# xen_teensy_motherboard_8cv8pt_mki.net
KiCad netlist of a schematic drawn in EAGLE
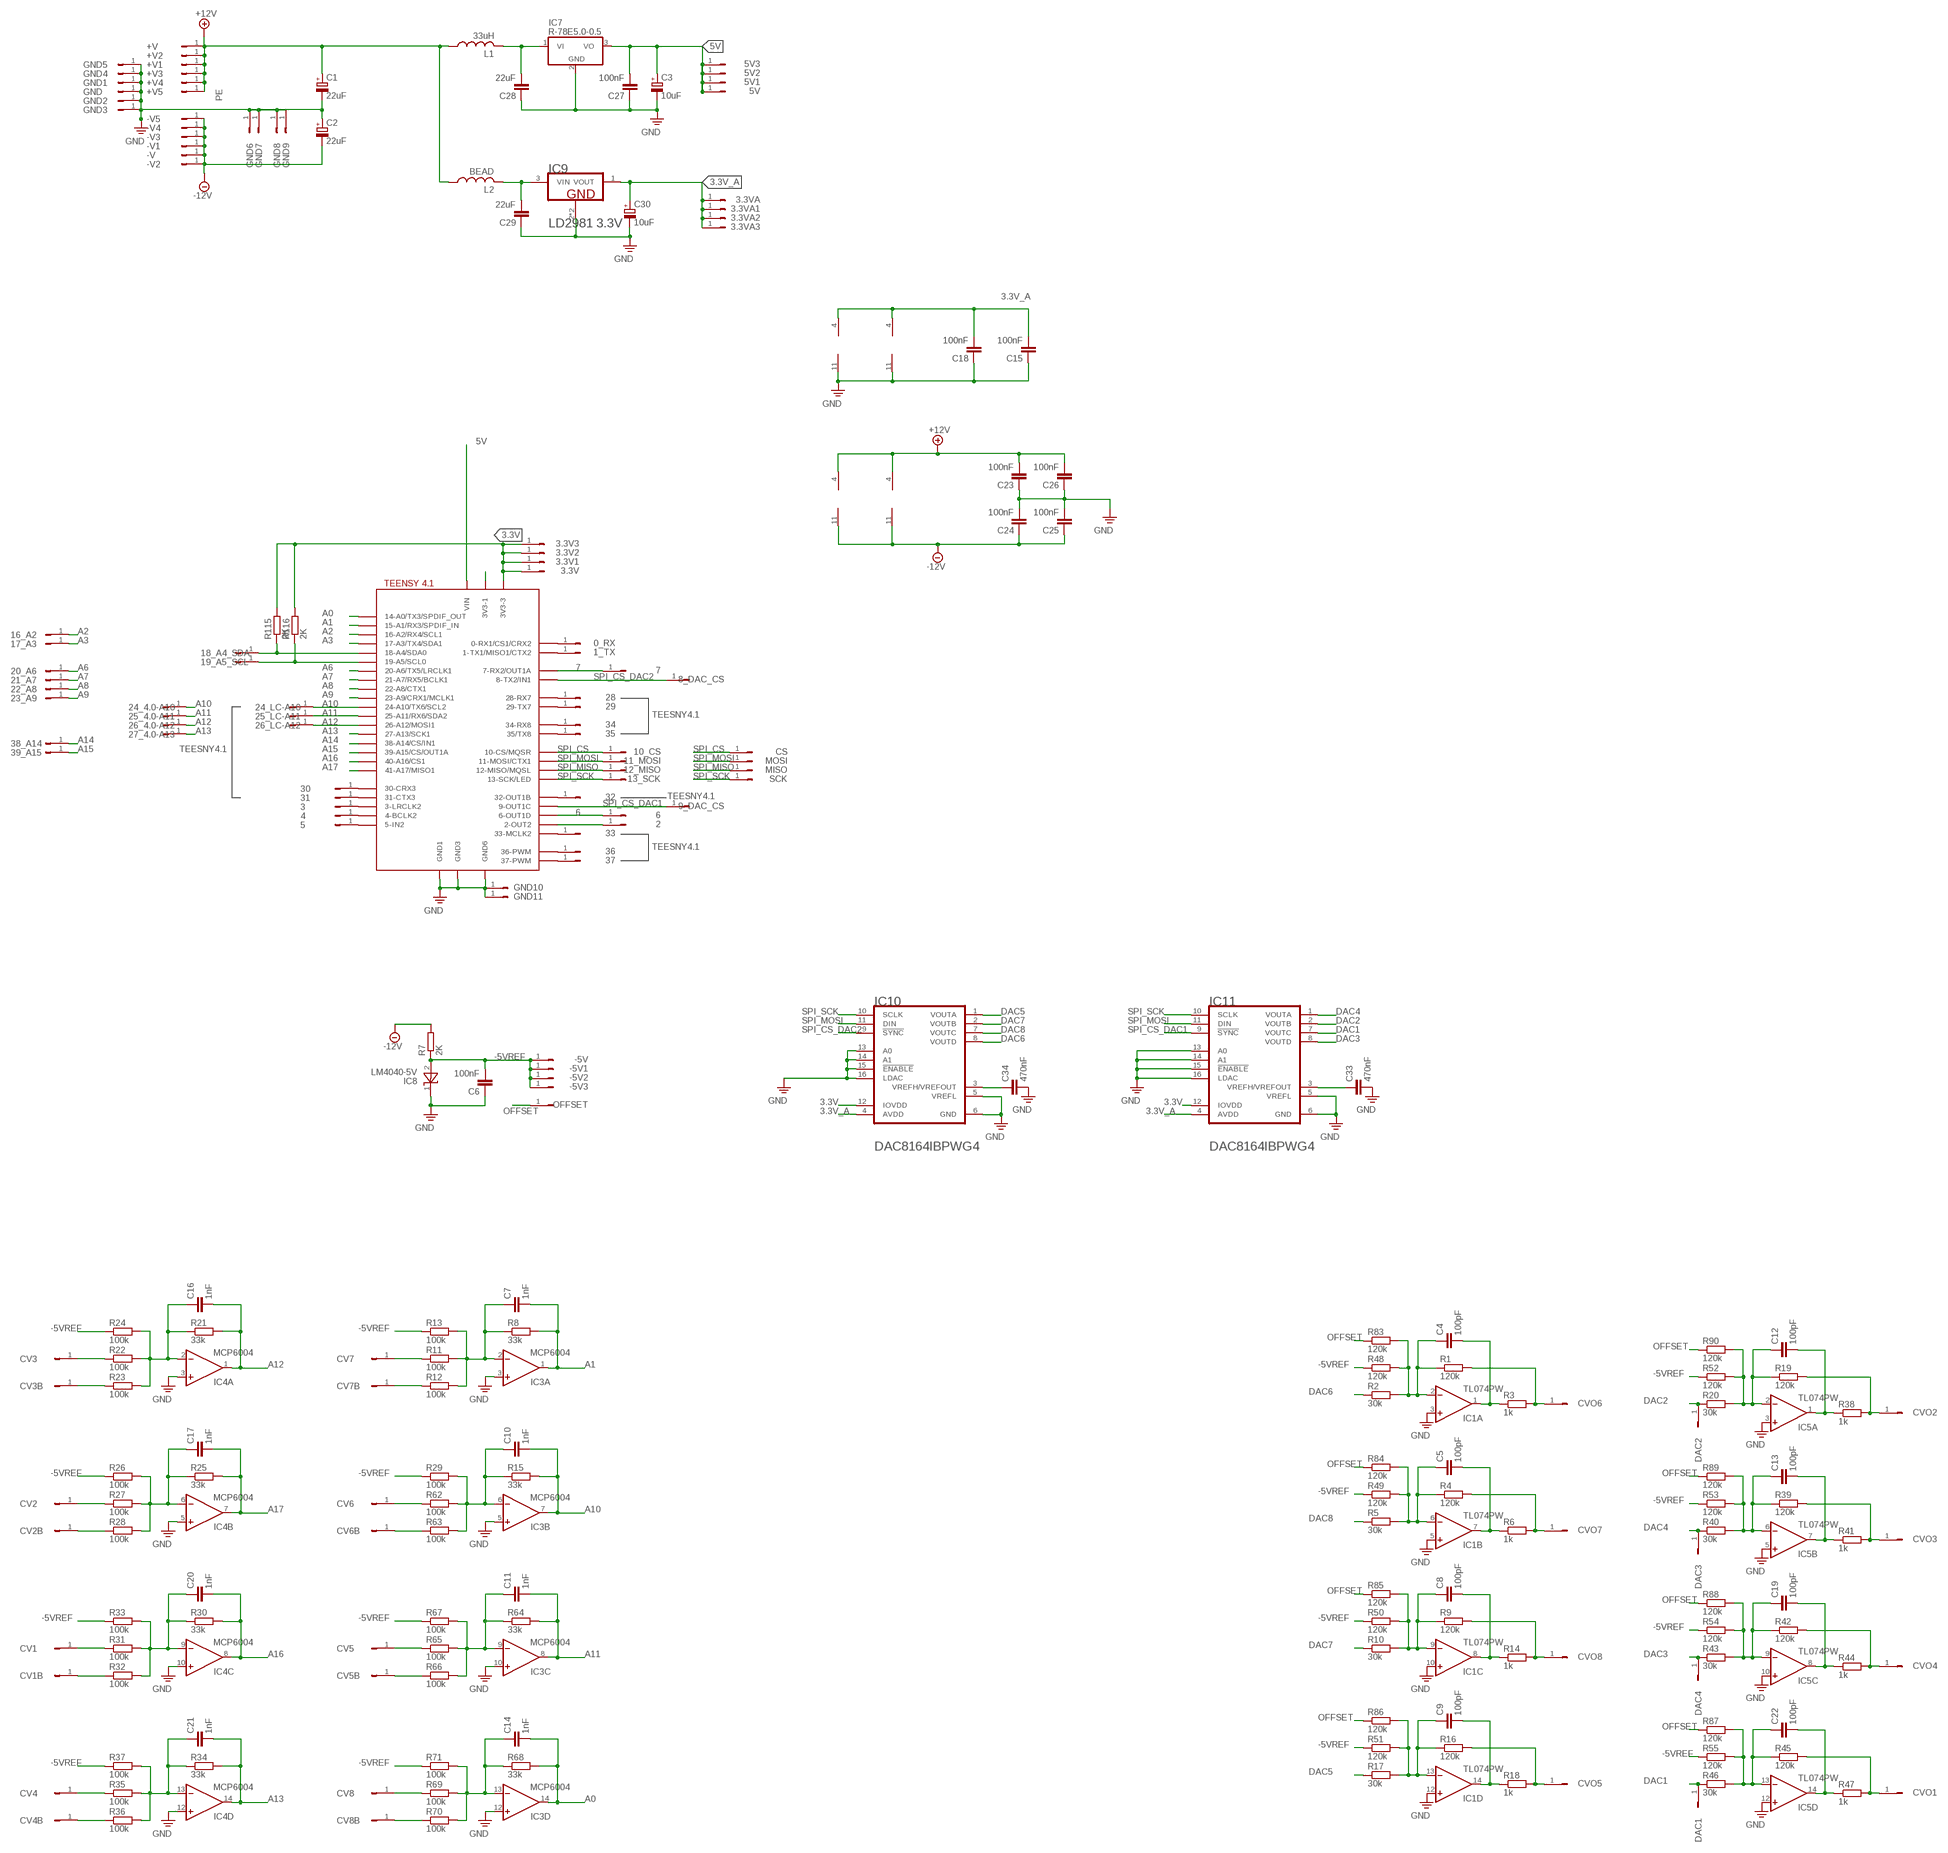
[diagram p0: schematic, sheet 1]

(export (version "E")
  (design (tool "Eeschema 10.0.6"))
  (components
    (comp (ref "+V")
      (value "HEADER/MALE/01")
      (footprint "eagle-import:HEADER_MALE_01")
      (fields (field (name "SPICEPREFIX") "X"))
      (libsource (lib "eagle-import") (part "HEADER/MALE/01"))
    )
    (comp (ref "+V1")
      (value "HEADER/MALE/01")
      (footprint "eagle-import:HEADER_MALE_01")
      (fields (field (name "SPICEPREFIX") "X"))
      (libsource (lib "eagle-import") (part "HEADER/MALE/01"))
    )
    (comp (ref "+V2")
      (value "HEADER/MALE/01")
      (footprint "eagle-import:HEADER_MALE_01")
      (fields (field (name "SPICEPREFIX") "X"))
      (libsource (lib "eagle-import") (part "HEADER/MALE/01"))
    )
    (comp (ref "+V3")
      (value "HEADER/MALE/01")
      (footprint "eagle-import:HEADER_MALE_01")
      (fields (field (name "SPICEPREFIX") "X"))
      (libsource (lib "eagle-import") (part "HEADER/MALE/01"))
    )
    (comp (ref "+V4")
      (value "HEADER/MALE/01")
      (footprint "eagle-import:HEADER_MALE_01")
      (fields (field (name "SPICEPREFIX") "X"))
      (libsource (lib "eagle-import") (part "HEADER/MALE/01"))
    )
    (comp (ref "+V5")
      (value "HEADER/MALE/01")
      (footprint "eagle-import:HEADER_MALE_01")
      (fields (field (name "SPICEPREFIX") "X"))
      (libsource (lib "eagle-import") (part "HEADER/MALE/01"))
    )
    (comp (ref "-5V")
      (value "HEADER/MALE/01")
      (footprint "eagle-import:HEADER_MALE_01")
      (fields (field (name "SPICEPREFIX") "X"))
      (libsource (lib "eagle-import") (part "HEADER/MALE/01"))
    )
    (comp (ref "-5V1")
      (value "HEADER/MALE/01")
      (footprint "eagle-import:HEADER_MALE_01")
      (fields (field (name "SPICEPREFIX") "X"))
      (libsource (lib "eagle-import") (part "HEADER/MALE/01"))
    )
    (comp (ref "-5V2")
      (value "HEADER/MALE/01")
      (footprint "eagle-import:HEADER_MALE_01")
      (fields (field (name "SPICEPREFIX") "X"))
      (libsource (lib "eagle-import") (part "HEADER/MALE/01"))
    )
    (comp (ref "-5V3")
      (value "HEADER/MALE/01")
      (footprint "eagle-import:HEADER_MALE_01")
      (fields (field (name "SPICEPREFIX") "X"))
      (libsource (lib "eagle-import") (part "HEADER/MALE/01"))
    )
    (comp (ref "-V")
      (value "HEADER/MALE/01")
      (footprint "eagle-import:HEADER_MALE_01")
      (fields (field (name "SPICEPREFIX") "X"))
      (libsource (lib "eagle-import") (part "HEADER/MALE/01"))
    )
    (comp (ref "-V1")
      (value "HEADER/MALE/01")
      (footprint "eagle-import:HEADER_MALE_01")
      (fields (field (name "SPICEPREFIX") "X"))
      (libsource (lib "eagle-import") (part "HEADER/MALE/01"))
    )
    (comp (ref "-V2")
      (value "HEADER/MALE/01")
      (footprint "eagle-import:HEADER_MALE_01")
      (fields (field (name "SPICEPREFIX") "X"))
      (libsource (lib "eagle-import") (part "HEADER/MALE/01"))
    )
    (comp (ref "-V3")
      (value "HEADER/MALE/01")
      (footprint "eagle-import:HEADER_MALE_01")
      (fields (field (name "SPICEPREFIX") "X"))
      (libsource (lib "eagle-import") (part "HEADER/MALE/01"))
    )
    (comp (ref "-V4")
      (value "HEADER/MALE/01")
      (footprint "eagle-import:HEADER_MALE_01")
      (fields (field (name "SPICEPREFIX") "X"))
      (libsource (lib "eagle-import") (part "HEADER/MALE/01"))
    )
    (comp (ref "-V5")
      (value "HEADER/MALE/01")
      (footprint "eagle-import:HEADER_MALE_01")
      (fields (field (name "SPICEPREFIX") "X"))
      (libsource (lib "eagle-import") (part "HEADER/MALE/01"))
    )
    (comp (ref "0_RX")
      (value "HEADER/MALE/01")
      (footprint "eagle-import:HEADER_MALE_01")
      (fields (field (name "SPICEPREFIX") "X"))
      (libsource (lib "eagle-import") (part "HEADER/MALE/01"))
    )
    (comp (ref "1_TX")
      (value "HEADER/MALE/01")
      (footprint "eagle-import:HEADER_MALE_01")
      (fields (field (name "SPICEPREFIX") "X"))
      (libsource (lib "eagle-import") (part "HEADER/MALE/01"))
    )
    (comp (ref "2")
      (value "HEADER/MALE/01")
      (footprint "eagle-import:HEADER_MALE_01")
      (fields (field (name "SPICEPREFIX") "X"))
      (libsource (lib "eagle-import") (part "HEADER/MALE/01"))
    )
    (comp (ref "3")
      (value "HEADER/MALE/01")
      (footprint "eagle-import:HEADER_MALE_01")
      (fields (field (name "SPICEPREFIX") "X"))
      (libsource (lib "eagle-import") (part "HEADER/MALE/01"))
    )
    (comp (ref "3.3V")
      (value "HEADER/MALE/01")
      (footprint "eagle-import:HEADER_MALE_01")
      (fields (field (name "SPICEPREFIX") "X"))
      (libsource (lib "eagle-import") (part "HEADER/MALE/01"))
    )
    (comp (ref "3.3V1")
      (value "HEADER/MALE/01")
      (footprint "eagle-import:HEADER_MALE_01")
      (fields (field (name "SPICEPREFIX") "X"))
      (libsource (lib "eagle-import") (part "HEADER/MALE/01"))
    )
    (comp (ref "3.3V2")
      (value "HEADER/MALE/01")
      (footprint "eagle-import:HEADER_MALE_01")
      (fields (field (name "SPICEPREFIX") "X"))
      (libsource (lib "eagle-import") (part "HEADER/MALE/01"))
    )
    (comp (ref "3.3V3")
      (value "HEADER/MALE/01")
      (footprint "eagle-import:HEADER_MALE_01")
      (fields (field (name "SPICEPREFIX") "X"))
      (libsource (lib "eagle-import") (part "HEADER/MALE/01"))
    )
    (comp (ref "3.3VA")
      (value "HEADER/MALE/01")
      (footprint "eagle-import:HEADER_MALE_01")
      (fields (field (name "SPICEPREFIX") "X"))
      (libsource (lib "eagle-import") (part "HEADER/MALE/01"))
    )
    (comp (ref "3.3VA1")
      (value "HEADER/MALE/01")
      (footprint "eagle-import:HEADER_MALE_01")
      (fields (field (name "SPICEPREFIX") "X"))
      (libsource (lib "eagle-import") (part "HEADER/MALE/01"))
    )
    (comp (ref "3.3VA2")
      (value "HEADER/MALE/01")
      (footprint "eagle-import:HEADER_MALE_01")
      (fields (field (name "SPICEPREFIX") "X"))
      (libsource (lib "eagle-import") (part "HEADER/MALE/01"))
    )
    (comp (ref "3.3VA3")
      (value "HEADER/MALE/01")
      (footprint "eagle-import:HEADER_MALE_01")
      (fields (field (name "SPICEPREFIX") "X"))
      (libsource (lib "eagle-import") (part "HEADER/MALE/01"))
    )
    (comp (ref "4")
      (value "HEADER/MALE/01")
      (footprint "eagle-import:HEADER_MALE_01")
      (fields (field (name "SPICEPREFIX") "X"))
      (libsource (lib "eagle-import") (part "HEADER/MALE/01"))
    )
    (comp (ref "5")
      (value "HEADER/MALE/01")
      (footprint "eagle-import:HEADER_MALE_01")
      (fields (field (name "SPICEPREFIX") "X"))
      (libsource (lib "eagle-import") (part "HEADER/MALE/01"))
    )
    (comp (ref "5V")
      (value "HEADER/MALE/01")
      (footprint "eagle-import:HEADER_MALE_01")
      (fields (field (name "SPICEPREFIX") "X"))
      (libsource (lib "eagle-import") (part "HEADER/MALE/01"))
    )
    (comp (ref "5V1")
      (value "HEADER/MALE/01")
      (footprint "eagle-import:HEADER_MALE_01")
      (fields (field (name "SPICEPREFIX") "X"))
      (libsource (lib "eagle-import") (part "HEADER/MALE/01"))
    )
    (comp (ref "5V2")
      (value "HEADER/MALE/01")
      (footprint "eagle-import:HEADER_MALE_01")
      (fields (field (name "SPICEPREFIX") "X"))
      (libsource (lib "eagle-import") (part "HEADER/MALE/01"))
    )
    (comp (ref "5V3")
      (value "HEADER/MALE/01")
      (footprint "eagle-import:HEADER_MALE_01")
      (fields (field (name "SPICEPREFIX") "X"))
      (libsource (lib "eagle-import") (part "HEADER/MALE/01"))
    )
    (comp (ref "6")
      (value "HEADER/MALE/01")
      (footprint "eagle-import:HEADER_MALE_01")
      (fields (field (name "SPICEPREFIX") "X"))
      (libsource (lib "eagle-import") (part "HEADER/MALE/01"))
    )
    (comp (ref "7")
      (value "HEADER/MALE/01")
      (footprint "eagle-import:HEADER_MALE_01")
      (fields (field (name "SPICEPREFIX") "X"))
      (libsource (lib "eagle-import") (part "HEADER/MALE/01"))
    )
    (comp (ref "8_DAC_CS")
      (value "HEADER/MALE/01")
      (footprint "eagle-import:HEADER_MALE_01")
      (fields (field (name "SPICEPREFIX") "X"))
      (libsource (lib "eagle-import") (part "HEADER/MALE/01"))
    )
    (comp (ref "9_DAC_CS")
      (value "HEADER/MALE/01")
      (footprint "eagle-import:HEADER_MALE_01")
      (fields (field (name "SPICEPREFIX") "X"))
      (libsource (lib "eagle-import") (part "HEADER/MALE/01"))
    )
    (comp (ref "10_CS")
      (value "HEADER/MALE/01")
      (footprint "eagle-import:HEADER_MALE_01")
      (fields (field (name "SPICEPREFIX") "X"))
      (libsource (lib "eagle-import") (part "HEADER/MALE/01"))
    )
    (comp (ref "11_MOSI")
      (value "HEADER/MALE/01")
      (footprint "eagle-import:HEADER_MALE_01")
      (fields (field (name "SPICEPREFIX") "X"))
      (libsource (lib "eagle-import") (part "HEADER/MALE/01"))
    )
    (comp (ref "12_MISO")
      (value "HEADER/MALE/01")
      (footprint "eagle-import:HEADER_MALE_01")
      (fields (field (name "SPICEPREFIX") "X"))
      (libsource (lib "eagle-import") (part "HEADER/MALE/01"))
    )
    (comp (ref "13_SCK")
      (value "HEADER/MALE/01")
      (footprint "eagle-import:HEADER_MALE_01")
      (fields (field (name "SPICEPREFIX") "X"))
      (libsource (lib "eagle-import") (part "HEADER/MALE/01"))
    )
    (comp (ref "16_A2")
      (value "HEADER/MALE/01")
      (footprint "eagle-import:HEADER_MALE_01")
      (fields (field (name "SPICEPREFIX") "X"))
      (libsource (lib "eagle-import") (part "HEADER/MALE/01"))
    )
    (comp (ref "17_A3")
      (value "HEADER/MALE/01")
      (footprint "eagle-import:HEADER_MALE_01")
      (fields (field (name "SPICEPREFIX") "X"))
      (libsource (lib "eagle-import") (part "HEADER/MALE/01"))
    )
    (comp (ref "18_A4_SDA")
      (value "HEADER/MALE/01")
      (footprint "eagle-import:HEADER_MALE_01")
      (fields (field (name "SPICEPREFIX") "X"))
      (libsource (lib "eagle-import") (part "HEADER/MALE/01"))
    )
    (comp (ref "19_A5_SCL")
      (value "HEADER/MALE/01")
      (footprint "eagle-import:HEADER_MALE_01")
      (fields (field (name "SPICEPREFIX") "X"))
      (libsource (lib "eagle-import") (part "HEADER/MALE/01"))
    )
    (comp (ref "20_A6")
      (value "HEADER/MALE/01")
      (footprint "eagle-import:HEADER_MALE_01")
      (fields (field (name "SPICEPREFIX") "X"))
      (libsource (lib "eagle-import") (part "HEADER/MALE/01"))
    )
    (comp (ref "21_A7")
      (value "HEADER/MALE/01")
      (footprint "eagle-import:HEADER_MALE_01")
      (fields (field (name "SPICEPREFIX") "X"))
      (libsource (lib "eagle-import") (part "HEADER/MALE/01"))
    )
    (comp (ref "22_A8")
      (value "HEADER/MALE/01")
      (footprint "eagle-import:HEADER_MALE_01")
      (fields (field (name "SPICEPREFIX") "X"))
      (libsource (lib "eagle-import") (part "HEADER/MALE/01"))
    )
    (comp (ref "23_A9")
      (value "HEADER/MALE/01")
      (footprint "eagle-import:HEADER_MALE_01")
      (fields (field (name "SPICEPREFIX") "X"))
      (libsource (lib "eagle-import") (part "HEADER/MALE/01"))
    )
    (comp (ref "24_4.0-A10")
      (value "HEADER/MALE/01")
      (footprint "eagle-import:HEADER_MALE_01")
      (fields (field (name "SPICEPREFIX") "X"))
      (libsource (lib "eagle-import") (part "HEADER/MALE/01"))
    )
    (comp (ref "24_LC-A10")
      (value "HEADER/MALE/01")
      (footprint "eagle-import:HEADER_MALE_01")
      (fields (field (name "SPICEPREFIX") "X"))
      (libsource (lib "eagle-import") (part "HEADER/MALE/01"))
    )
    (comp (ref "25_4.0-A11")
      (value "HEADER/MALE/01")
      (footprint "eagle-import:HEADER_MALE_01")
      (fields (field (name "SPICEPREFIX") "X"))
      (libsource (lib "eagle-import") (part "HEADER/MALE/01"))
    )
    (comp (ref "25_LC-A11")
      (value "HEADER/MALE/01")
      (footprint "eagle-import:HEADER_MALE_01")
      (fields (field (name "SPICEPREFIX") "X"))
      (libsource (lib "eagle-import") (part "HEADER/MALE/01"))
    )
    (comp (ref "26_4.0-A12")
      (value "HEADER/MALE/01")
      (footprint "eagle-import:HEADER_MALE_01")
      (fields (field (name "SPICEPREFIX") "X"))
      (libsource (lib "eagle-import") (part "HEADER/MALE/01"))
    )
    (comp (ref "26_LC-A12")
      (value "HEADER/MALE/01")
      (footprint "eagle-import:HEADER_MALE_01")
      (fields (field (name "SPICEPREFIX") "X"))
      (libsource (lib "eagle-import") (part "HEADER/MALE/01"))
    )
    (comp (ref "27_4.0-A13")
      (value "HEADER/MALE/01")
      (footprint "eagle-import:HEADER_MALE_01")
      (fields (field (name "SPICEPREFIX") "X"))
      (libsource (lib "eagle-import") (part "HEADER/MALE/01"))
    )
    (comp (ref "28")
      (value "HEADER/MALE/01")
      (footprint "eagle-import:HEADER_MALE_01")
      (fields (field (name "SPICEPREFIX") "X"))
      (libsource (lib "eagle-import") (part "HEADER/MALE/01"))
    )
    (comp (ref "29")
      (value "HEADER/MALE/01")
      (footprint "eagle-import:HEADER_MALE_01")
      (fields (field (name "SPICEPREFIX") "X"))
      (libsource (lib "eagle-import") (part "HEADER/MALE/01"))
    )
    (comp (ref "30")
      (value "HEADER/MALE/01")
      (footprint "eagle-import:HEADER_MALE_01")
      (fields (field (name "SPICEPREFIX") "X"))
      (libsource (lib "eagle-import") (part "HEADER/MALE/01"))
    )
    (comp (ref "31")
      (value "HEADER/MALE/01")
      (footprint "eagle-import:HEADER_MALE_01")
      (fields (field (name "SPICEPREFIX") "X"))
      (libsource (lib "eagle-import") (part "HEADER/MALE/01"))
    )
    (comp (ref "32")
      (value "HEADER/MALE/01")
      (footprint "eagle-import:HEADER_MALE_01")
      (fields (field (name "SPICEPREFIX") "X"))
      (libsource (lib "eagle-import") (part "HEADER/MALE/01"))
    )
    (comp (ref "33")
      (value "HEADER/MALE/01")
      (footprint "eagle-import:HEADER_MALE_01")
      (fields (field (name "SPICEPREFIX") "X"))
      (libsource (lib "eagle-import") (part "HEADER/MALE/01"))
    )
    (comp (ref "34")
      (value "HEADER/MALE/01")
      (footprint "eagle-import:HEADER_MALE_01")
      (fields (field (name "SPICEPREFIX") "X"))
      (libsource (lib "eagle-import") (part "HEADER/MALE/01"))
    )
    (comp (ref "35")
      (value "HEADER/MALE/01")
      (footprint "eagle-import:HEADER_MALE_01")
      (fields (field (name "SPICEPREFIX") "X"))
      (libsource (lib "eagle-import") (part "HEADER/MALE/01"))
    )
    (comp (ref "36")
      (value "HEADER/MALE/01")
      (footprint "eagle-import:HEADER_MALE_01")
      (fields (field (name "SPICEPREFIX") "X"))
      (libsource (lib "eagle-import") (part "HEADER/MALE/01"))
    )
    (comp (ref "37")
      (value "HEADER/MALE/01")
      (footprint "eagle-import:HEADER_MALE_01")
      (fields (field (name "SPICEPREFIX") "X"))
      (libsource (lib "eagle-import") (part "HEADER/MALE/01"))
    )
    (comp (ref "38_A14")
      (value "HEADER/MALE/01")
      (footprint "eagle-import:HEADER_MALE_01")
      (fields (field (name "SPICEPREFIX") "X"))
      (libsource (lib "eagle-import") (part "HEADER/MALE/01"))
    )
    (comp (ref "39_A15")
      (value "HEADER/MALE/01")
      (footprint "eagle-import:HEADER_MALE_01")
      (fields (field (name "SPICEPREFIX") "X"))
      (libsource (lib "eagle-import") (part "HEADER/MALE/01"))
    )
    (comp (ref "C1")
      (value "22uF")
      (footprint "eagle-import:SV-C")
      (fields (field (name "SPICEPREFIX") "C"))
      (libsource (lib "eagle-import") (part "CAPACITOR/POLARIZEDSMDC"))
    )
    (comp (ref "C2")
      (value "22uF")
      (footprint "eagle-import:SV-C")
      (fields (field (name "SPICEPREFIX") "C"))
      (libsource (lib "eagle-import") (part "CAPACITOR/POLARIZEDSMDC"))
    )
    (comp (ref "C3")
      (value "10uF")
      (footprint "eagle-import:SV-B")
      (fields (field (name "SPICEPREFIX") "C"))
      (libsource (lib "eagle-import") (part "CAPACITOR/POLARIZEDSMDB"))
    )
    (comp (ref "C4")
      (value "100pF")
      (footprint "eagle-import:C0603")
      (libsource (lib "eagle-import") (part "CAPACITORC0603"))
    )
    (comp (ref "C5")
      (value "100pF")
      (footprint "eagle-import:C0603")
      (libsource (lib "eagle-import") (part "CAPACITORC0603"))
    )
    (comp (ref "C6")
      (value "100nF")
      (footprint "eagle-import:C0603")
      (libsource (lib "eagle-import") (part "CAPACITORC0603"))
    )
    (comp (ref "C7")
      (value "1nF")
      (footprint "eagle-import:C0603")
      (libsource (lib "eagle-import") (part "CAPACITORC0603"))
    )
    (comp (ref "C8")
      (value "100pF")
      (footprint "eagle-import:C0603")
      (libsource (lib "eagle-import") (part "CAPACITORC0603"))
    )
    (comp (ref "C9")
      (value "100pF")
      (footprint "eagle-import:C0603")
      (libsource (lib "eagle-import") (part "CAPACITORC0603"))
    )
    (comp (ref "C10")
      (value "1nF")
      (footprint "eagle-import:C0603")
      (libsource (lib "eagle-import") (part "CAPACITORC0603"))
    )
    (comp (ref "C11")
      (value "1nF")
      (footprint "eagle-import:C0603")
      (libsource (lib "eagle-import") (part "CAPACITORC0603"))
    )
    (comp (ref "C12")
      (value "100pF")
      (footprint "eagle-import:C0603")
      (libsource (lib "eagle-import") (part "CAPACITORC0603"))
    )
    (comp (ref "C13")
      (value "100pF")
      (footprint "eagle-import:C0603")
      (libsource (lib "eagle-import") (part "CAPACITORC0603"))
    )
    (comp (ref "C14")
      (value "1nF")
      (footprint "eagle-import:C0603")
      (libsource (lib "eagle-import") (part "CAPACITORC0603"))
    )
    (comp (ref "C15")
      (value "100nF")
      (footprint "eagle-import:C0603")
      (libsource (lib "eagle-import") (part "CAPACITORC0603"))
    )
    (comp (ref "C16")
      (value "1nF")
      (footprint "eagle-import:C0603")
      (libsource (lib "eagle-import") (part "CAPACITORC0603"))
    )
    (comp (ref "C17")
      (value "1nF")
      (footprint "eagle-import:C0603")
      (libsource (lib "eagle-import") (part "CAPACITORC0603"))
    )
    (comp (ref "C18")
      (value "100nF")
      (footprint "eagle-import:C0603")
      (libsource (lib "eagle-import") (part "CAPACITORC0603"))
    )
    (comp (ref "C19")
      (value "100pF")
      (footprint "eagle-import:C0603")
      (libsource (lib "eagle-import") (part "CAPACITORC0603"))
    )
    (comp (ref "C20")
      (value "1nF")
      (footprint "eagle-import:C0603")
      (libsource (lib "eagle-import") (part "CAPACITORC0603"))
    )
    (comp (ref "C21")
      (value "1nF")
      (footprint "eagle-import:C0603")
      (libsource (lib "eagle-import") (part "CAPACITORC0603"))
    )
    (comp (ref "C22")
      (value "100pF")
      (footprint "eagle-import:C0603")
      (libsource (lib "eagle-import") (part "CAPACITORC0603"))
    )
    (comp (ref "C23")
      (value "100nF")
      (footprint "eagle-import:C0603")
      (libsource (lib "eagle-import") (part "CAPACITORC0603"))
    )
    (comp (ref "C24")
      (value "100nF")
      (footprint "eagle-import:C0603")
      (libsource (lib "eagle-import") (part "CAPACITORC0603"))
    )
    (comp (ref "C25")
      (value "100nF")
      (footprint "eagle-import:C0603")
      (libsource (lib "eagle-import") (part "CAPACITORC0603"))
    )
    (comp (ref "C26")
      (value "100nF")
      (footprint "eagle-import:C0603")
      (libsource (lib "eagle-import") (part "CAPACITORC0603"))
    )
    (comp (ref "C27")
      (value "100nF")
      (footprint "eagle-import:C0603")
      (libsource (lib "eagle-import") (part "CAPACITORC0603"))
    )
    (comp (ref "C28")
      (value "22uF")
      (footprint "eagle-import:C0805")
      (libsource (lib "eagle-import") (part "CAPACITORC0805"))
    )
    (comp (ref "C29")
      (value "22uF")
      (footprint "eagle-import:C0805")
      (libsource (lib "eagle-import") (part "CAPACITORC0805"))
    )
    (comp (ref "C30")
      (value "10uF")
      (footprint "eagle-import:SV-B")
      (fields (field (name "SPICEPREFIX") "C"))
      (libsource (lib "eagle-import") (part "CAPACITOR/POLARIZEDSMDB"))
    )
    (comp (ref "C33")
      (value "470nF")
      (footprint "eagle-import:C0603")
      (libsource (lib "eagle-import") (part "CAPACITORC0603"))
    )
    (comp (ref "C34")
      (value "470nF")
      (footprint "eagle-import:C0603")
      (libsource (lib "eagle-import") (part "CAPACITORC0603"))
    )
    (comp (ref "CS")
      (value "HEADER/MALE/01")
      (footprint "eagle-import:HEADER_MALE_01")
      (fields (field (name "SPICEPREFIX") "X"))
      (libsource (lib "eagle-import") (part "HEADER/MALE/01"))
    )
    (comp (ref "CV1")
      (value "HEADER/MALE/01")
      (footprint "eagle-import:HEADER_MALE_01")
      (fields (field (name "SPICEPREFIX") "X"))
      (libsource (lib "eagle-import") (part "HEADER/MALE/01"))
    )
    (comp (ref "CV1B")
      (value "HEADER/MALE/01")
      (footprint "eagle-import:HEADER_MALE_01")
      (fields (field (name "SPICEPREFIX") "X"))
      (libsource (lib "eagle-import") (part "HEADER/MALE/01"))
    )
    (comp (ref "CV2")
      (value "HEADER/MALE/01")
      (footprint "eagle-import:HEADER_MALE_01")
      (fields (field (name "SPICEPREFIX") "X"))
      (libsource (lib "eagle-import") (part "HEADER/MALE/01"))
    )
    (comp (ref "CV2B")
      (value "HEADER/MALE/01")
      (footprint "eagle-import:HEADER_MALE_01")
      (fields (field (name "SPICEPREFIX") "X"))
      (libsource (lib "eagle-import") (part "HEADER/MALE/01"))
    )
    (comp (ref "CV3")
      (value "HEADER/MALE/01")
      (footprint "eagle-import:HEADER_MALE_01")
      (fields (field (name "SPICEPREFIX") "X"))
      (libsource (lib "eagle-import") (part "HEADER/MALE/01"))
    )
    (comp (ref "CV3B")
      (value "HEADER/MALE/01")
      (footprint "eagle-import:HEADER_MALE_01")
      (fields (field (name "SPICEPREFIX") "X"))
      (libsource (lib "eagle-import") (part "HEADER/MALE/01"))
    )
    (comp (ref "CV4")
      (value "HEADER/MALE/01")
      (footprint "eagle-import:HEADER_MALE_01")
      (fields (field (name "SPICEPREFIX") "X"))
      (libsource (lib "eagle-import") (part "HEADER/MALE/01"))
    )
    (comp (ref "CV4B")
      (value "HEADER/MALE/01")
      (footprint "eagle-import:HEADER_MALE_01")
      (fields (field (name "SPICEPREFIX") "X"))
      (libsource (lib "eagle-import") (part "HEADER/MALE/01"))
    )
    (comp (ref "CV5")
      (value "HEADER/MALE/01")
      (footprint "eagle-import:HEADER_MALE_01")
      (fields (field (name "SPICEPREFIX") "X"))
      (libsource (lib "eagle-import") (part "HEADER/MALE/01"))
    )
    (comp (ref "CV5B")
      (value "HEADER/MALE/01")
      (footprint "eagle-import:HEADER_MALE_01")
      (fields (field (name "SPICEPREFIX") "X"))
      (libsource (lib "eagle-import") (part "HEADER/MALE/01"))
    )
    (comp (ref "CV6")
      (value "HEADER/MALE/01")
      (footprint "eagle-import:HEADER_MALE_01")
      (fields (field (name "SPICEPREFIX") "X"))
      (libsource (lib "eagle-import") (part "HEADER/MALE/01"))
    )
    (comp (ref "CV6B")
      (value "HEADER/MALE/01")
      (footprint "eagle-import:HEADER_MALE_01")
      (fields (field (name "SPICEPREFIX") "X"))
      (libsource (lib "eagle-import") (part "HEADER/MALE/01"))
    )
    (comp (ref "CV7")
      (value "HEADER/MALE/01")
      (footprint "eagle-import:HEADER_MALE_01")
      (fields (field (name "SPICEPREFIX") "X"))
      (libsource (lib "eagle-import") (part "HEADER/MALE/01"))
    )
    (comp (ref "CV7B")
      (value "HEADER/MALE/01")
      (footprint "eagle-import:HEADER_MALE_01")
      (fields (field (name "SPICEPREFIX") "X"))
      (libsource (lib "eagle-import") (part "HEADER/MALE/01"))
    )
    (comp (ref "CV8")
      (value "HEADER/MALE/01")
      (footprint "eagle-import:HEADER_MALE_01")
      (fields (field (name "SPICEPREFIX") "X"))
      (libsource (lib "eagle-import") (part "HEADER/MALE/01"))
    )
    (comp (ref "CV8B")
      (value "HEADER/MALE/01")
      (footprint "eagle-import:HEADER_MALE_01")
      (fields (field (name "SPICEPREFIX") "X"))
      (libsource (lib "eagle-import") (part "HEADER/MALE/01"))
    )
    (comp (ref "CVO1")
      (value "HEADER/MALE/01")
      (footprint "eagle-import:HEADER_MALE_01")
      (fields (field (name "SPICEPREFIX") "X"))
      (libsource (lib "eagle-import") (part "HEADER/MALE/01"))
    )
    (comp (ref "CVO2")
      (value "HEADER/MALE/01")
      (footprint "eagle-import:HEADER_MALE_01")
      (fields (field (name "SPICEPREFIX") "X"))
      (libsource (lib "eagle-import") (part "HEADER/MALE/01"))
    )
    (comp (ref "CVO3")
      (value "HEADER/MALE/01")
      (footprint "eagle-import:HEADER_MALE_01")
      (fields (field (name "SPICEPREFIX") "X"))
      (libsource (lib "eagle-import") (part "HEADER/MALE/01"))
    )
    (comp (ref "CVO4")
      (value "HEADER/MALE/01")
      (footprint "eagle-import:HEADER_MALE_01")
      (fields (field (name "SPICEPREFIX") "X"))
      (libsource (lib "eagle-import") (part "HEADER/MALE/01"))
    )
    (comp (ref "CVO5")
      (value "HEADER/MALE/01")
      (footprint "eagle-import:HEADER_MALE_01")
      (fields (field (name "SPICEPREFIX") "X"))
      (libsource (lib "eagle-import") (part "HEADER/MALE/01"))
    )
    (comp (ref "CVO6")
      (value "HEADER/MALE/01")
      (footprint "eagle-import:HEADER_MALE_01")
      (fields (field (name "SPICEPREFIX") "X"))
      (libsource (lib "eagle-import") (part "HEADER/MALE/01"))
    )
    (comp (ref "CVO7")
      (value "HEADER/MALE/01")
      (footprint "eagle-import:HEADER_MALE_01")
      (fields (field (name "SPICEPREFIX") "X"))
      (libsource (lib "eagle-import") (part "HEADER/MALE/01"))
    )
    (comp (ref "CVO8")
      (value "HEADER/MALE/01")
      (footprint "eagle-import:HEADER_MALE_01")
      (fields (field (name "SPICEPREFIX") "X"))
      (libsource (lib "eagle-import") (part "HEADER/MALE/01"))
    )
    (comp (ref "DAC1")
      (value "HEADER/MALE/01")
      (footprint "eagle-import:HEADER_MALE_01")
      (fields (field (name "SPICEPREFIX") "X"))
      (libsource (lib "eagle-import") (part "HEADER/MALE/01"))
    )
    (comp (ref "DAC2")
      (value "HEADER/MALE/01")
      (footprint "eagle-import:HEADER_MALE_01")
      (fields (field (name "SPICEPREFIX") "X"))
      (libsource (lib "eagle-import") (part "HEADER/MALE/01"))
    )
    (comp (ref "DAC3")
      (value "HEADER/MALE/01")
      (footprint "eagle-import:HEADER_MALE_01")
      (fields (field (name "SPICEPREFIX") "X"))
      (libsource (lib "eagle-import") (part "HEADER/MALE/01"))
    )
    (comp (ref "DAC4")
      (value "HEADER/MALE/01")
      (footprint "eagle-import:HEADER_MALE_01")
      (fields (field (name "SPICEPREFIX") "X"))
      (libsource (lib "eagle-import") (part "HEADER/MALE/01"))
    )
    (comp (ref "GND")
      (value "HEADER/MALE/01")
      (footprint "eagle-import:HEADER_MALE_01")
      (fields (field (name "SPICEPREFIX") "X"))
      (libsource (lib "eagle-import") (part "HEADER/MALE/01"))
    )
    (comp (ref "GND1")
      (value "HEADER/MALE/01")
      (footprint "eagle-import:HEADER_MALE_01")
      (fields (field (name "SPICEPREFIX") "X"))
      (libsource (lib "eagle-import") (part "HEADER/MALE/01"))
    )
    (comp (ref "GND2")
      (value "HEADER/MALE/01")
      (footprint "eagle-import:HEADER_MALE_01")
      (fields (field (name "SPICEPREFIX") "X"))
      (libsource (lib "eagle-import") (part "HEADER/MALE/01"))
    )
    (comp (ref "GND3")
      (value "HEADER/MALE/01")
      (footprint "eagle-import:HEADER_MALE_01")
      (fields (field (name "SPICEPREFIX") "X"))
      (libsource (lib "eagle-import") (part "HEADER/MALE/01"))
    )
    (comp (ref "GND4")
      (value "HEADER/MALE/01")
      (footprint "eagle-import:HEADER_MALE_01")
      (fields (field (name "SPICEPREFIX") "X"))
      (libsource (lib "eagle-import") (part "HEADER/MALE/01"))
    )
    (comp (ref "GND5")
      (value "HEADER/MALE/01")
      (footprint "eagle-import:HEADER_MALE_01")
      (fields (field (name "SPICEPREFIX") "X"))
      (libsource (lib "eagle-import") (part "HEADER/MALE/01"))
    )
    (comp (ref "GND6")
      (value "HEADER/MALE/01")
      (footprint "eagle-import:HEADER_MALE_01")
      (fields (field (name "SPICEPREFIX") "X"))
      (libsource (lib "eagle-import") (part "HEADER/MALE/01"))
    )
    (comp (ref "GND7")
      (value "HEADER/MALE/01")
      (footprint "eagle-import:HEADER_MALE_01")
      (fields (field (name "SPICEPREFIX") "X"))
      (libsource (lib "eagle-import") (part "HEADER/MALE/01"))
    )
    (comp (ref "GND8")
      (value "HEADER/MALE/01")
      (footprint "eagle-import:HEADER_MALE_01")
      (fields (field (name "SPICEPREFIX") "X"))
      (libsource (lib "eagle-import") (part "HEADER/MALE/01"))
    )
    (comp (ref "GND9")
      (value "HEADER/MALE/01")
      (footprint "eagle-import:HEADER_MALE_01")
      (fields (field (name "SPICEPREFIX") "X"))
      (libsource (lib "eagle-import") (part "HEADER/MALE/01"))
    )
    (comp (ref "GND10")
      (value "HEADER/MALE/01")
      (footprint "eagle-import:HEADER_MALE_01")
      (fields (field (name "SPICEPREFIX") "X"))
      (libsource (lib "eagle-import") (part "HEADER/MALE/01"))
    )
    (comp (ref "GND11")
      (value "HEADER/MALE/01")
      (footprint "eagle-import:HEADER_MALE_01")
      (fields (field (name "SPICEPREFIX") "X"))
      (libsource (lib "eagle-import") (part "HEADER/MALE/01"))
    )
    (comp (ref "IC1")
      (value "TL074PW")
      (footprint "eagle-import:TSSOP14")
      (libsource (lib "eagle-import") (part "TL074PW"))
    )
    (comp (ref "IC3")
      (value "MCP6004")
      (footprint "eagle-import:TSSOP14")
      (libsource (lib "eagle-import") (part "TL074PW"))
    )
    (comp (ref "IC4")
      (value "MCP6004")
      (footprint "eagle-import:TSSOP14")
      (libsource (lib "eagle-import") (part "TL074PW"))
    )
    (comp (ref "IC5")
      (value "TL074PW")
      (footprint "eagle-import:TSSOP14")
      (libsource (lib "eagle-import") (part "TL074PW"))
    )
    (comp (ref "IC6")
      (value "TEENSY41-OUTER")
      (footprint "eagle-import:TENNSY41-OUTER")
      (libsource (lib "eagle-import") (part "TEENSY41-OUTER"))
    )
    (comp (ref "IC7")
      (value "R-78E5.0-0.5")
      (footprint "eagle-import:WE78")
      (libsource (lib "eagle-import") (part "WE173950378"))
    )
    (comp (ref "IC8")
      (value "LM4040-5V")
      (footprint "eagle-import:SOT-23")
      (libsource (lib "eagle-import") (part "LM4040CYM3-2.5"))
    )
    (comp (ref "IC9")
      (value "LD2981 3.3V")
      (footprint "eagle-import:LD2981-SOT89")
      (fields (field (name "MF") "STMicroelectronics") (field (name "MPN") "LD2981CU33TR"))
      (libsource (lib "eagle-import") (part "LD2981LD2981-SOT89"))
    )
    (comp (ref "IC10")
      (value "DAC8164")
      (footprint "eagle-import:TEXAS_INSTRUMENTS_DAC8164IBPWG4_1")
      (fields (field (name "MF") "Texas Instruments") (field (name "MPN") "DAC8164IBPWG4"))
      (libsource (lib "eagle-import") (part "TEXAS_INSTRUMENTS_DAC8164IBPWG4TEXAS_INSTRUMENTS_DAC8164IBPWG4_0_1"))
    )
    (comp (ref "IC11")
      (value "DAC8164")
      (footprint "eagle-import:TEXAS_INSTRUMENTS_DAC8164IBPWG4_1")
      (fields (field (name "MF") "Texas Instruments") (field (name "MPN") "DAC8164IBPWG4"))
      (libsource (lib "eagle-import") (part "TEXAS_INSTRUMENTS_DAC8164IBPWG4TEXAS_INSTRUMENTS_DAC8164IBPWG4_0_1"))
    )
    (comp (ref "L1")
      (value "33uH")
      (footprint "eagle-import:L2012C")
      (libsource (lib "eagle-import") (part "INDUCTORL2012C"))
    )
    (comp (ref "L2")
      (value "BEAD")
      (footprint "eagle-import:R0603")
      (libsource (lib "eagle-import") (part "INDUCTORL0603"))
    )
    (comp (ref "MISO")
      (value "HEADER/MALE/01")
      (footprint "eagle-import:HEADER_MALE_01")
      (fields (field (name "SPICEPREFIX") "X"))
      (libsource (lib "eagle-import") (part "HEADER/MALE/01"))
    )
    (comp (ref "MOSI")
      (value "HEADER/MALE/01")
      (footprint "eagle-import:HEADER_MALE_01")
      (fields (field (name "SPICEPREFIX") "X"))
      (libsource (lib "eagle-import") (part "HEADER/MALE/01"))
    )
    (comp (ref "OFFSET")
      (value "HEADER/MALE/01")
      (footprint "eagle-import:HEADER_MALE_01")
      (fields (field (name "SPICEPREFIX") "X"))
      (libsource (lib "eagle-import") (part "HEADER/MALE/01"))
    )
    (comp (ref "R1")
      (value "120k")
      (footprint "eagle-import:R0603")
      (libsource (lib "eagle-import") (part "RESISTOR"))
    )
    (comp (ref "R2")
      (value "30k")
      (footprint "eagle-import:R0603")
      (libsource (lib "eagle-import") (part "RESISTOR"))
    )
    (comp (ref "R3")
      (value "1k")
      (footprint "eagle-import:R0603")
      (libsource (lib "eagle-import") (part "RESISTOR"))
    )
    (comp (ref "R4")
      (value "120k")
      (footprint "eagle-import:R0603")
      (libsource (lib "eagle-import") (part "RESISTOR"))
    )
    (comp (ref "R5")
      (value "30k")
      (footprint "eagle-import:R0603")
      (libsource (lib "eagle-import") (part "RESISTOR"))
    )
    (comp (ref "R6")
      (value "1k")
      (footprint "eagle-import:R0603")
      (libsource (lib "eagle-import") (part "RESISTOR"))
    )
    (comp (ref "R7")
      (value "2K")
      (footprint "eagle-import:R0603")
      (libsource (lib "eagle-import") (part "RESISTOR"))
    )
    (comp (ref "R8")
      (value "33k")
      (footprint "eagle-import:R0603")
      (libsource (lib "eagle-import") (part "RESISTOR"))
    )
    (comp (ref "R9")
      (value "120k")
      (footprint "eagle-import:R0603")
      (libsource (lib "eagle-import") (part "RESISTOR"))
    )
    (comp (ref "R10")
      (value "30k")
      (footprint "eagle-import:R0603")
      (libsource (lib "eagle-import") (part "RESISTOR"))
    )
    (comp (ref "R11")
      (value "100k")
      (footprint "eagle-import:R0603")
      (libsource (lib "eagle-import") (part "RESISTOR"))
    )
    (comp (ref "R12")
      (value "100k")
      (footprint "eagle-import:R0603")
      (libsource (lib "eagle-import") (part "RESISTOR"))
    )
    (comp (ref "R13")
      (value "100k")
      (footprint "eagle-import:R0603")
      (libsource (lib "eagle-import") (part "RESISTOR"))
    )
    (comp (ref "R14")
      (value "1k")
      (footprint "eagle-import:R0603")
      (libsource (lib "eagle-import") (part "RESISTOR"))
    )
    (comp (ref "R15")
      (value "33k")
      (footprint "eagle-import:R0603")
      (libsource (lib "eagle-import") (part "RESISTOR"))
    )
    (comp (ref "R16")
      (value "120k")
      (footprint "eagle-import:R0603")
      (libsource (lib "eagle-import") (part "RESISTOR"))
    )
    (comp (ref "R17")
      (value "30k")
      (footprint "eagle-import:R0603")
      (libsource (lib "eagle-import") (part "RESISTOR"))
    )
    (comp (ref "R18")
      (value "1k")
      (footprint "eagle-import:R0603")
      (libsource (lib "eagle-import") (part "RESISTOR"))
    )
    (comp (ref "R19")
      (value "120k")
      (footprint "eagle-import:R0603")
      (libsource (lib "eagle-import") (part "RESISTOR"))
    )
    (comp (ref "R20")
      (value "30k")
      (footprint "eagle-import:R0603")
      (libsource (lib "eagle-import") (part "RESISTOR"))
    )
    (comp (ref "R21")
      (value "33k")
      (footprint "eagle-import:R0603")
      (libsource (lib "eagle-import") (part "RESISTOR"))
    )
    (comp (ref "R22")
      (value "100k")
      (footprint "eagle-import:R0603")
      (libsource (lib "eagle-import") (part "RESISTOR"))
    )
    (comp (ref "R23")
      (value "100k")
      (footprint "eagle-import:R0603")
      (libsource (lib "eagle-import") (part "RESISTOR"))
    )
    (comp (ref "R24")
      (value "100k")
      (footprint "eagle-import:R0603")
      (libsource (lib "eagle-import") (part "RESISTOR"))
    )
    (comp (ref "R25")
      (value "33k")
      (footprint "eagle-import:R0603")
      (libsource (lib "eagle-import") (part "RESISTOR"))
    )
    (comp (ref "R26")
      (value "100k")
      (footprint "eagle-import:R0603")
      (libsource (lib "eagle-import") (part "RESISTOR"))
    )
    (comp (ref "R27")
      (value "100k")
      (footprint "eagle-import:R0603")
      (libsource (lib "eagle-import") (part "RESISTOR"))
    )
    (comp (ref "R28")
      (value "100k")
      (footprint "eagle-import:R0603")
      (libsource (lib "eagle-import") (part "RESISTOR"))
    )
    (comp (ref "R29")
      (value "100k")
      (footprint "eagle-import:R0603")
      (libsource (lib "eagle-import") (part "RESISTOR"))
    )
    (comp (ref "R30")
      (value "33k")
      (footprint "eagle-import:R0603")
      (libsource (lib "eagle-import") (part "RESISTOR"))
    )
    (comp (ref "R31")
      (value "100k")
      (footprint "eagle-import:R0603")
      (libsource (lib "eagle-import") (part "RESISTOR"))
    )
    (comp (ref "R32")
      (value "100k")
      (footprint "eagle-import:R0603")
      (libsource (lib "eagle-import") (part "RESISTOR"))
    )
    (comp (ref "R33")
      (value "100k")
      (footprint "eagle-import:R0603")
      (libsource (lib "eagle-import") (part "RESISTOR"))
    )
    (comp (ref "R34")
      (value "33k")
      (footprint "eagle-import:R0603")
      (libsource (lib "eagle-import") (part "RESISTOR"))
    )
    (comp (ref "R35")
      (value "100k")
      (footprint "eagle-import:R0603")
      (libsource (lib "eagle-import") (part "RESISTOR"))
    )
    (comp (ref "R36")
      (value "100k")
      (footprint "eagle-import:R0603")
      (libsource (lib "eagle-import") (part "RESISTOR"))
    )
    (comp (ref "R37")
      (value "100k")
      (footprint "eagle-import:R0603")
      (libsource (lib "eagle-import") (part "RESISTOR"))
    )
    (comp (ref "R38")
      (value "1k")
      (footprint "eagle-import:R0603")
      (libsource (lib "eagle-import") (part "RESISTOR"))
    )
    (comp (ref "R39")
      (value "120k")
      (footprint "eagle-import:R0603")
      (libsource (lib "eagle-import") (part "RESISTOR"))
    )
    (comp (ref "R40")
      (value "30k")
      (footprint "eagle-import:R0603")
      (libsource (lib "eagle-import") (part "RESISTOR"))
    )
    (comp (ref "R41")
      (value "1k")
      (footprint "eagle-import:R0603")
      (libsource (lib "eagle-import") (part "RESISTOR"))
    )
    (comp (ref "R42")
      (value "120k")
      (footprint "eagle-import:R0603")
      (libsource (lib "eagle-import") (part "RESISTOR"))
    )
    (comp (ref "R43")
      (value "30k")
      (footprint "eagle-import:R0603")
      (libsource (lib "eagle-import") (part "RESISTOR"))
    )
    (comp (ref "R44")
      (value "1k")
      (footprint "eagle-import:R0603")
      (libsource (lib "eagle-import") (part "RESISTOR"))
    )
    (comp (ref "R45")
      (value "120k")
      (footprint "eagle-import:R0603")
      (libsource (lib "eagle-import") (part "RESISTOR"))
    )
    (comp (ref "R46")
      (value "30k")
      (footprint "eagle-import:R0603")
      (libsource (lib "eagle-import") (part "RESISTOR"))
    )
    (comp (ref "R47")
      (value "1k")
      (footprint "eagle-import:R0603")
      (libsource (lib "eagle-import") (part "RESISTOR"))
    )
    (comp (ref "R48")
      (value "120k")
      (footprint "eagle-import:R0603")
      (libsource (lib "eagle-import") (part "RESISTOR"))
    )
    (comp (ref "R49")
      (value "120k")
      (footprint "eagle-import:R0603")
      (libsource (lib "eagle-import") (part "RESISTOR"))
    )
    (comp (ref "R50")
      (value "120k")
      (footprint "eagle-import:R0603")
      (libsource (lib "eagle-import") (part "RESISTOR"))
    )
    (comp (ref "R51")
      (value "120k")
      (footprint "eagle-import:R0603")
      (libsource (lib "eagle-import") (part "RESISTOR"))
    )
    (comp (ref "R52")
      (value "120k")
      (footprint "eagle-import:R0603")
      (libsource (lib "eagle-import") (part "RESISTOR"))
    )
    (comp (ref "R53")
      (value "120k")
      (footprint "eagle-import:R0603")
      (libsource (lib "eagle-import") (part "RESISTOR"))
    )
    (comp (ref "R54")
      (value "120k")
      (footprint "eagle-import:R0603")
      (libsource (lib "eagle-import") (part "RESISTOR"))
    )
    (comp (ref "R55")
      (value "120k")
      (footprint "eagle-import:R0603")
      (libsource (lib "eagle-import") (part "RESISTOR"))
    )
    (comp (ref "R62")
      (value "100k")
      (footprint "eagle-import:R0603")
      (libsource (lib "eagle-import") (part "RESISTOR"))
    )
    (comp (ref "R63")
      (value "100k")
      (footprint "eagle-import:R0603")
      (libsource (lib "eagle-import") (part "RESISTOR"))
    )
    (comp (ref "R64")
      (value "33k")
      (footprint "eagle-import:R0603")
      (libsource (lib "eagle-import") (part "RESISTOR"))
    )
    (comp (ref "R65")
      (value "100k")
      (footprint "eagle-import:R0603")
      (libsource (lib "eagle-import") (part "RESISTOR"))
    )
    (comp (ref "R66")
      (value "100k")
      (footprint "eagle-import:R0603")
      (libsource (lib "eagle-import") (part "RESISTOR"))
    )
    (comp (ref "R67")
      (value "100k")
      (footprint "eagle-import:R0603")
      (libsource (lib "eagle-import") (part "RESISTOR"))
    )
    (comp (ref "R68")
      (value "33k")
      (footprint "eagle-import:R0603")
      (libsource (lib "eagle-import") (part "RESISTOR"))
    )
    (comp (ref "R69")
      (value "100k")
      (footprint "eagle-import:R0603")
      (libsource (lib "eagle-import") (part "RESISTOR"))
    )
    (comp (ref "R70")
      (value "100k")
      (footprint "eagle-import:R0603")
      (libsource (lib "eagle-import") (part "RESISTOR"))
    )
    (comp (ref "R71")
      (value "100k")
      (footprint "eagle-import:R0603")
      (libsource (lib "eagle-import") (part "RESISTOR"))
    )
    (comp (ref "R83")
      (value "120k")
      (footprint "eagle-import:R0603")
      (libsource (lib "eagle-import") (part "RESISTOR"))
    )
    (comp (ref "R84")
      (value "120k")
      (footprint "eagle-import:R0603")
      (libsource (lib "eagle-import") (part "RESISTOR"))
    )
    (comp (ref "R85")
      (value "120k")
      (footprint "eagle-import:R0603")
      (libsource (lib "eagle-import") (part "RESISTOR"))
    )
    (comp (ref "R86")
      (value "120k")
      (footprint "eagle-import:R0603")
      (libsource (lib "eagle-import") (part "RESISTOR"))
    )
    (comp (ref "R87")
      (value "120k")
      (footprint "eagle-import:R0603")
      (libsource (lib "eagle-import") (part "RESISTOR"))
    )
    (comp (ref "R88")
      (value "120k")
      (footprint "eagle-import:R0603")
      (libsource (lib "eagle-import") (part "RESISTOR"))
    )
    (comp (ref "R89")
      (value "120k")
      (footprint "eagle-import:R0603")
      (libsource (lib "eagle-import") (part "RESISTOR"))
    )
    (comp (ref "R90")
      (value "120k")
      (footprint "eagle-import:R0603")
      (libsource (lib "eagle-import") (part "RESISTOR"))
    )
    (comp (ref "R115")
      (value "2K")
      (footprint "eagle-import:R0603")
      (libsource (lib "eagle-import") (part "RESISTOR"))
    )
    (comp (ref "R116")
      (value "2K")
      (footprint "eagle-import:R0603")
      (libsource (lib "eagle-import") (part "RESISTOR"))
    )
    (comp (ref "SCK")
      (value "HEADER/MALE/01")
      (footprint "eagle-import:HEADER_MALE_01")
      (fields (field (name "SPICEPREFIX") "X"))
      (libsource (lib "eagle-import") (part "HEADER/MALE/01"))
    )
  )
  (nets
    (net (code "1") (name "+12V") (class "Default")
      (node (ref "+V") (pin "1") (pinfunction "3_1") (pintype "passive"))
      (node (ref "+V1") (pin "1") (pinfunction "3_1") (pintype "passive"))
      (node (ref "+V2") (pin "1") (pinfunction "3_1") (pintype "passive"))
      (node (ref "+V3") (pin "1") (pinfunction "3_1") (pintype "passive"))
      (node (ref "+V4") (pin "1") (pinfunction "3_1") (pintype "passive"))
      (node (ref "+V5") (pin "1") (pinfunction "3_1") (pintype "passive"))
      (node (ref "C1") (pin "+") (pinfunction "+_+") (pintype "passive"))
      (node (ref "C23") (pin "2") (pinfunction "2_2") (pintype "passive"))
      (node (ref "C26") (pin "2") (pinfunction "2_2") (pintype "passive"))
      (node (ref "IC1") (pin "4") (pinfunction "V+_4") (pintype "power_in"))
      (node (ref "IC5") (pin "4") (pinfunction "V+_4") (pintype "power_in"))
      (node (ref "L1") (pin "1") (pinfunction "1_1") (pintype "passive"))
      (node (ref "L2") (pin "1") (pinfunction "1_1") (pintype "passive"))
    )
    (net (code "2") (name "-12V") (class "Default")
      (node (ref "-V") (pin "1") (pinfunction "3_1") (pintype "passive"))
      (node (ref "-V1") (pin "1") (pinfunction "3_1") (pintype "passive"))
      (node (ref "-V2") (pin "1") (pinfunction "3_1") (pintype "passive"))
      (node (ref "-V3") (pin "1") (pinfunction "3_1") (pintype "passive"))
      (node (ref "-V4") (pin "1") (pinfunction "3_1") (pintype "passive"))
      (node (ref "-V5") (pin "1") (pinfunction "3_1") (pintype "passive"))
      (node (ref "C2") (pin "-") (pinfunction "-_-") (pintype "passive"))
      (node (ref "C24") (pin "1") (pinfunction "1_1") (pintype "passive"))
      (node (ref "C25") (pin "1") (pinfunction "1_1") (pintype "passive"))
      (node (ref "IC1") (pin "11") (pinfunction "V-_11") (pintype "power_in"))
      (node (ref "IC5") (pin "11") (pinfunction "V-_11") (pintype "power_in"))
      (node (ref "R7") (pin "2") (pinfunction "2_2") (pintype "passive"))
    )
    (net (code "3") (name "/-5VREF") (class "Default")
      (node (ref "-5V") (pin "1") (pinfunction "3_1") (pintype "passive"))
      (node (ref "-5V1") (pin "1") (pinfunction "3_1") (pintype "passive"))
      (node (ref "-5V2") (pin "1") (pinfunction "3_1") (pintype "passive"))
      (node (ref "-5V3") (pin "1") (pinfunction "3_1") (pintype "passive"))
      (node (ref "C6") (pin "2") (pinfunction "2_2") (pintype "passive"))
      (node (ref "IC8") (pin "2") (pinfunction "A_2") (pintype "output"))
      (node (ref "R13") (pin "1") (pinfunction "1_1") (pintype "passive"))
      (node (ref "R24") (pin "1") (pinfunction "1_1") (pintype "passive"))
      (node (ref "R26") (pin "1") (pinfunction "1_1") (pintype "passive"))
      (node (ref "R29") (pin "1") (pinfunction "1_1") (pintype "passive"))
      (node (ref "R33") (pin "1") (pinfunction "1_1") (pintype "passive"))
      (node (ref "R37") (pin "1") (pinfunction "1_1") (pintype "passive"))
      (node (ref "R48") (pin "1") (pinfunction "1_1") (pintype "passive"))
      (node (ref "R49") (pin "1") (pinfunction "1_1") (pintype "passive"))
      (node (ref "R50") (pin "1") (pinfunction "1_1") (pintype "passive"))
      (node (ref "R51") (pin "1") (pinfunction "1_1") (pintype "passive"))
      (node (ref "R52") (pin "1") (pinfunction "1_1") (pintype "passive"))
      (node (ref "R53") (pin "1") (pinfunction "1_1") (pintype "passive"))
      (node (ref "R54") (pin "1") (pinfunction "1_1") (pintype "passive"))
      (node (ref "R55") (pin "1") (pinfunction "1_1") (pintype "passive"))
      (node (ref "R67") (pin "1") (pinfunction "1_1") (pintype "passive"))
      (node (ref "R7") (pin "1") (pinfunction "1_1") (pintype "passive"))
      (node (ref "R71") (pin "1") (pinfunction "1_1") (pintype "passive"))
    )
    (net (code "4") (name "/6") (class "Default")
      (node (ref "6") (pin "1") (pinfunction "3_1") (pintype "passive"))
      (node (ref "IC6") (pin "6-OUT1D") (pinfunction "6-OUT1D_6-OUT1D") (pintype "bidirectional"))
    )
    (net (code "5") (name "/7") (class "Default")
      (node (ref "7") (pin "1") (pinfunction "3_1") (pintype "passive"))
      (node (ref "IC6") (pin "7-RX2/OUT1A") (pinfunction "7-RX2/OUT1A_7-RX2/OUT1A") (pintype "bidirectional"))
    )
    (net (code "6") (name "/A0") (class "Default")
      (node (ref "C14") (pin "2") (pinfunction "2_2") (pintype "passive"))
      (node (ref "IC3") (pin "14") (pinfunction "OUT_14") (pintype "output"))
      (node (ref "IC6") (pin "14-A0/TX3/SPDIF_OUT") (pinfunction "14-A0/TX3/SPDIF_OUT_14-A0/TX3/SPDIF_OUT") (pintype "bidirectional"))
      (node (ref "R68") (pin "2") (pinfunction "2_2") (pintype "passive"))
    )
    (net (code "7") (name "/A1") (class "Default")
      (node (ref "C7") (pin "2") (pinfunction "2_2") (pintype "passive"))
      (node (ref "IC3") (pin "1") (pinfunction "OUT_1") (pintype "output"))
      (node (ref "IC6") (pin "15-A1/RX3/SPDIF_IN") (pinfunction "15-A1/RX3/SPDIF_IN_15-A1/RX3/SPDIF_IN") (pintype "bidirectional"))
      (node (ref "R8") (pin "2") (pinfunction "2_2") (pintype "passive"))
    )
    (net (code "8") (name "/A2") (class "Default")
      (node (ref "16_A2") (pin "1") (pinfunction "3_1") (pintype "passive"))
      (node (ref "IC6") (pin "16-A2/RX4/SCL1") (pinfunction "16-A2/RX4/SCL1_16-A2/RX4/SCL1") (pintype "bidirectional"))
    )
    (net (code "9") (name "/A3") (class "Default")
      (node (ref "17_A3") (pin "1") (pinfunction "3_1") (pintype "passive"))
      (node (ref "IC6") (pin "17-A3/TX4/SDA1") (pinfunction "17-A3/TX4/SDA1_17-A3/TX4/SDA1") (pintype "bidirectional"))
    )
    (net (code "10") (name "/A6") (class "Default")
      (node (ref "20_A6") (pin "1") (pinfunction "3_1") (pintype "passive"))
      (node (ref "IC6") (pin "20-A6/TX5/LRCLK1") (pinfunction "20-A6/TX5/LRCLK1_20-A6/TX5/LRCLK1") (pintype "bidirectional"))
    )
    (net (code "11") (name "/A7") (class "Default")
      (node (ref "21_A7") (pin "1") (pinfunction "3_1") (pintype "passive"))
      (node (ref "IC6") (pin "21-A7/RX5/BCLK1") (pinfunction "21-A7/RX5/BCLK1_21-A7/RX5/BCLK1") (pintype "bidirectional"))
    )
    (net (code "12") (name "/A8") (class "Default")
      (node (ref "22_A8") (pin "1") (pinfunction "3_1") (pintype "passive"))
      (node (ref "IC6") (pin "22-A8/CTX1") (pinfunction "22-A8/CTX1_22-A8/CTX1") (pintype "bidirectional"))
    )
    (net (code "13") (name "/A9") (class "Default")
      (node (ref "23_A9") (pin "1") (pinfunction "3_1") (pintype "passive"))
      (node (ref "IC6") (pin "23-A9/CRX1/MCLK1") (pinfunction "23-A9/CRX1/MCLK1_23-A9/CRX1/MCLK1") (pintype "bidirectional"))
    )
    (net (code "14") (name "/A10") (class "Default")
      (node (ref "24_4.0-A10") (pin "1") (pinfunction "3_1") (pintype "passive"))
      (node (ref "24_LC-A10") (pin "1") (pinfunction "3_1") (pintype "passive"))
      (node (ref "C10") (pin "2") (pinfunction "2_2") (pintype "passive"))
      (node (ref "IC3") (pin "7") (pinfunction "OUT_7") (pintype "output"))
      (node (ref "IC6") (pin "24-A10/TX6/SCL2") (pinfunction "24-A10/TX6/SCL2_24-A10/TX6/SCL2") (pintype "bidirectional"))
      (node (ref "R15") (pin "2") (pinfunction "2_2") (pintype "passive"))
    )
    (net (code "15") (name "/A11") (class "Default")
      (node (ref "25_4.0-A11") (pin "1") (pinfunction "3_1") (pintype "passive"))
      (node (ref "25_LC-A11") (pin "1") (pinfunction "3_1") (pintype "passive"))
      (node (ref "C11") (pin "2") (pinfunction "2_2") (pintype "passive"))
      (node (ref "IC3") (pin "8") (pinfunction "OUT_8") (pintype "output"))
      (node (ref "IC6") (pin "25-A11/RX6/SDA2") (pinfunction "25-A11/RX6/SDA2_25-A11/RX6/SDA2") (pintype "bidirectional"))
      (node (ref "R64") (pin "2") (pinfunction "2_2") (pintype "passive"))
    )
    (net (code "16") (name "/A12") (class "Default")
      (node (ref "26_4.0-A12") (pin "1") (pinfunction "3_1") (pintype "passive"))
      (node (ref "26_LC-A12") (pin "1") (pinfunction "3_1") (pintype "passive"))
      (node (ref "C16") (pin "2") (pinfunction "2_2") (pintype "passive"))
      (node (ref "IC4") (pin "1") (pinfunction "OUT_1") (pintype "output"))
      (node (ref "IC6") (pin "26-A12/MOSI1") (pinfunction "26-A12/MOSI1_26-A12/MOSI1") (pintype "bidirectional"))
      (node (ref "R21") (pin "2") (pinfunction "2_2") (pintype "passive"))
    )
    (net (code "17") (name "/A13") (class "Default")
      (node (ref "27_4.0-A13") (pin "1") (pinfunction "3_1") (pintype "passive"))
      (node (ref "C21") (pin "2") (pinfunction "2_2") (pintype "passive"))
      (node (ref "IC4") (pin "14") (pinfunction "OUT_14") (pintype "output"))
      (node (ref "IC6") (pin "27-A13/SCK1") (pinfunction "27-A13/SCK1_27-A13/SCK1") (pintype "bidirectional"))
      (node (ref "R34") (pin "2") (pinfunction "2_2") (pintype "passive"))
    )
    (net (code "18") (name "/A14") (class "Default")
      (node (ref "38_A14") (pin "1") (pinfunction "3_1") (pintype "passive"))
      (node (ref "IC6") (pin "38-A14/CS/IN1") (pinfunction "38-A14/CS/IN1_38-A14/CS/IN1") (pintype "bidirectional"))
    )
    (net (code "19") (name "/A15") (class "Default")
      (node (ref "39_A15") (pin "1") (pinfunction "3_1") (pintype "passive"))
      (node (ref "IC6") (pin "39-A15/CS/OUT1A") (pinfunction "39-A15/CS/OUT1A_39-A15/CS/OUT1A") (pintype "bidirectional"))
    )
    (net (code "20") (name "/A16") (class "Default")
      (node (ref "C20") (pin "2") (pinfunction "2_2") (pintype "passive"))
      (node (ref "IC4") (pin "8") (pinfunction "OUT_8") (pintype "output"))
      (node (ref "IC6") (pin "40-A16/CS1") (pinfunction "40-A16/CS1_40-A16/CS1") (pintype "bidirectional"))
      (node (ref "R30") (pin "2") (pinfunction "2_2") (pintype "passive"))
    )
    (net (code "21") (name "/A17") (class "Default")
      (node (ref "C17") (pin "2") (pinfunction "2_2") (pintype "passive"))
      (node (ref "IC4") (pin "7") (pinfunction "OUT_7") (pintype "output"))
      (node (ref "IC6") (pin "41-A17/MISO1") (pinfunction "41-A17/MISO1_41-A17/MISO1") (pintype "bidirectional"))
      (node (ref "R25") (pin "2") (pinfunction "2_2") (pintype "passive"))
    )
    (net (code "22") (name "/DAC1") (class "Default")
      (node (ref "DAC1") (pin "1") (pinfunction "3_1") (pintype "passive"))
      (node (ref "IC11") (pin "7") (pinfunction "VOUTC_7") (pintype "tri_state"))
      (node (ref "R46") (pin "1") (pinfunction "1_1") (pintype "passive"))
    )
    (net (code "23") (name "/DAC2") (class "Default")
      (node (ref "DAC2") (pin "1") (pinfunction "3_1") (pintype "passive"))
      (node (ref "IC11") (pin "2") (pinfunction "VOUTB_2") (pintype "tri_state"))
      (node (ref "R20") (pin "1") (pinfunction "1_1") (pintype "passive"))
    )
    (net (code "24") (name "/DAC3") (class "Default")
      (node (ref "DAC4") (pin "1") (pinfunction "3_1") (pintype "passive"))
      (node (ref "IC11") (pin "8") (pinfunction "VOUTD_8") (pintype "tri_state"))
      (node (ref "R43") (pin "1") (pinfunction "1_1") (pintype "passive"))
    )
    (net (code "25") (name "/DAC4") (class "Default")
      (node (ref "DAC3") (pin "1") (pinfunction "3_1") (pintype "passive"))
      (node (ref "IC11") (pin "1") (pinfunction "VOUTA_1") (pintype "tri_state"))
      (node (ref "R40") (pin "1") (pinfunction "1_1") (pintype "passive"))
    )
    (net (code "26") (name "/DAC5") (class "Default")
      (node (ref "IC10") (pin "1") (pinfunction "VOUTA_1") (pintype "tri_state"))
      (node (ref "R17") (pin "1") (pinfunction "1_1") (pintype "passive"))
    )
    (net (code "27") (name "/DAC6") (class "Default")
      (node (ref "IC10") (pin "8") (pinfunction "VOUTD_8") (pintype "tri_state"))
      (node (ref "R2") (pin "1") (pinfunction "1_1") (pintype "passive"))
    )
    (net (code "28") (name "/DAC7") (class "Default")
      (node (ref "IC10") (pin "2") (pinfunction "VOUTB_2") (pintype "tri_state"))
      (node (ref "R10") (pin "1") (pinfunction "1_1") (pintype "passive"))
    )
    (net (code "29") (name "/DAC8") (class "Default")
      (node (ref "IC10") (pin "7") (pinfunction "VOUTC_7") (pintype "tri_state"))
      (node (ref "R5") (pin "1") (pinfunction "1_1") (pintype "passive"))
    )
    (net (code "30") (name "/OFFSET") (class "Default")
      (node (ref "OFFSET") (pin "1") (pinfunction "3_1") (pintype "passive"))
      (node (ref "R83") (pin "1") (pinfunction "1_1") (pintype "passive"))
      (node (ref "R84") (pin "1") (pinfunction "1_1") (pintype "passive"))
      (node (ref "R85") (pin "1") (pinfunction "1_1") (pintype "passive"))
      (node (ref "R86") (pin "1") (pinfunction "1_1") (pintype "passive"))
      (node (ref "R87") (pin "1") (pinfunction "1_1") (pintype "passive"))
      (node (ref "R88") (pin "1") (pinfunction "1_1") (pintype "passive"))
      (node (ref "R89") (pin "1") (pinfunction "1_1") (pintype "passive"))
      (node (ref "R90") (pin "1") (pinfunction "1_1") (pintype "passive"))
    )
    (net (code "31") (name "/SPI_CS") (class "Default")
      (node (ref "10_CS") (pin "1") (pinfunction "3_1") (pintype "passive"))
      (node (ref "CS") (pin "1") (pinfunction "3_1") (pintype "passive"))
      (node (ref "IC6") (pin "10-CS\\MQSR") (pinfunction "10-CS/MQSR_10-CS\\MQSR") (pintype "bidirectional"))
    )
    (net (code "32") (name "/SPI_CS_DAC1") (class "Default")
      (node (ref "9_DAC_CS") (pin "1") (pinfunction "3_1") (pintype "passive"))
      (node (ref "IC11") (pin "9") (pinfunction "~{SYNC}_9") (pintype "input"))
      (node (ref "IC6") (pin "9-OUT1C") (pinfunction "9-OUT1C_9-OUT1C") (pintype "bidirectional"))
    )
    (net (code "33") (name "/SPI_CS_DAC2") (class "Default")
      (node (ref "8_DAC_CS") (pin "1") (pinfunction "3_1") (pintype "passive"))
      (node (ref "IC10") (pin "9") (pinfunction "~{SYNC}_9") (pintype "input"))
      (node (ref "IC6") (pin "8-TX2/IN1") (pinfunction "8-TX2/IN1_8-TX2/IN1") (pintype "bidirectional"))
    )
    (net (code "34") (name "/SPI_MISO") (class "Default")
      (node (ref "12_MISO") (pin "1") (pinfunction "3_1") (pintype "passive"))
      (node (ref "IC6") (pin "12-MISO/MQSL") (pinfunction "12-MISO/MQSL_12-MISO/MQSL") (pintype "bidirectional"))
      (node (ref "MISO") (pin "1") (pinfunction "3_1") (pintype "passive"))
    )
    (net (code "35") (name "/SPI_MOSI") (class "Default")
      (node (ref "11_MOSI") (pin "1") (pinfunction "3_1") (pintype "passive"))
      (node (ref "IC10") (pin "11") (pinfunction "DIN_11") (pintype "input"))
      (node (ref "IC11") (pin "11") (pinfunction "DIN_11") (pintype "input"))
      (node (ref "IC6") (pin "11-MOSI/CTX1") (pinfunction "11-MOSI/CTX1_11-MOSI/CTX1") (pintype "bidirectional"))
      (node (ref "MOSI") (pin "1") (pinfunction "3_1") (pintype "passive"))
    )
    (net (code "36") (name "/SPI_SCK") (class "Default")
      (node (ref "13_SCK") (pin "1") (pinfunction "3_1") (pintype "passive"))
      (node (ref "IC10") (pin "10") (pinfunction "SCLK_10") (pintype "input"))
      (node (ref "IC11") (pin "10") (pinfunction "SCLK_10") (pintype "input"))
      (node (ref "IC6") (pin "13-SCK/LED") (pinfunction "13-SCK/LED_13-SCK/LED") (pintype "bidirectional"))
      (node (ref "SCK") (pin "1") (pinfunction "3_1") (pintype "passive"))
    )
    (net (code "37") (name "3.3V") (class "Default")
      (node (ref "3.3V") (pin "1") (pinfunction "3_1") (pintype "passive"))
      (node (ref "3.3V1") (pin "1") (pinfunction "3_1") (pintype "passive"))
      (node (ref "3.3V2") (pin "1") (pinfunction "3_1") (pintype "passive"))
      (node (ref "3.3V3") (pin "1") (pinfunction "3_1") (pintype "passive"))
      (node (ref "IC10") (pin "12") (pinfunction "IOVDD_12") (pintype "power_in"))
      (node (ref "IC11") (pin "12") (pinfunction "IOVDD_12") (pintype "power_in"))
      (node (ref "IC6") (pin "3V3-3") (pinfunction "3V3-3_3V3-3") (pintype "bidirectional"))
      (node (ref "R115") (pin "2") (pinfunction "2_2") (pintype "passive"))
      (node (ref "R116") (pin "2") (pinfunction "2_2") (pintype "passive"))
    )
    (net (code "38") (name "3.3V_A") (class "Default")
      (node (ref "3.3VA") (pin "1") (pinfunction "3_1") (pintype "passive"))
      (node (ref "3.3VA1") (pin "1") (pinfunction "3_1") (pintype "passive"))
      (node (ref "3.3VA2") (pin "1") (pinfunction "3_1") (pintype "passive"))
      (node (ref "3.3VA3") (pin "1") (pinfunction "3_1") (pintype "passive"))
      (node (ref "C15") (pin "2") (pinfunction "2_2") (pintype "passive"))
      (node (ref "C18") (pin "2") (pinfunction "2_2") (pintype "passive"))
      (node (ref "C30") (pin "+") (pinfunction "+_+") (pintype "passive"))
      (node (ref "IC10") (pin "4") (pinfunction "AVDD_4") (pintype "power_in"))
      (node (ref "IC11") (pin "4") (pinfunction "AVDD_4") (pintype "power_in"))
      (node (ref "IC3") (pin "4") (pinfunction "V+_4") (pintype "power_in"))
      (node (ref "IC4") (pin "4") (pinfunction "V+_4") (pintype "power_in"))
      (node (ref "IC9") (pin "1") (pinfunction "VOUT_1") (pintype "power_in"))
    )
    (net (code "39") (name "5V") (class "Default")
      (node (ref "5V") (pin "1") (pinfunction "3_1") (pintype "passive"))
      (node (ref "5V1") (pin "1") (pinfunction "3_1") (pintype "passive"))
      (node (ref "5V2") (pin "1") (pinfunction "3_1") (pintype "passive"))
      (node (ref "5V3") (pin "1") (pinfunction "3_1") (pintype "passive"))
      (node (ref "C27") (pin "2") (pinfunction "2_2") (pintype "passive"))
      (node (ref "C3") (pin "+") (pinfunction "+_+") (pintype "passive"))
      (node (ref "IC6") (pin "VIN") (pinfunction "VIN_VIN") (pintype "bidirectional"))
      (node (ref "IC7") (pin "3") (pinfunction "VO_3") (pintype "passive"))
    )
    (net (code "40") (name "GND") (class "Default")
      (node (ref "C1") (pin "-") (pinfunction "-_-") (pintype "passive"))
      (node (ref "C15") (pin "1") (pinfunction "1_1") (pintype "passive"))
      (node (ref "C18") (pin "1") (pinfunction "1_1") (pintype "passive"))
      (node (ref "C2") (pin "+") (pinfunction "+_+") (pintype "passive"))
      (node (ref "C23") (pin "1") (pinfunction "1_1") (pintype "passive"))
      (node (ref "C24") (pin "2") (pinfunction "2_2") (pintype "passive"))
      (node (ref "C25") (pin "2") (pinfunction "2_2") (pintype "passive"))
      (node (ref "C26") (pin "1") (pinfunction "1_1") (pintype "passive"))
      (node (ref "C27") (pin "1") (pinfunction "1_1") (pintype "passive"))
      (node (ref "C28") (pin "1") (pinfunction "1_1") (pintype "passive"))
      (node (ref "C29") (pin "1") (pinfunction "1_1") (pintype "passive"))
      (node (ref "C3") (pin "-") (pinfunction "-_-") (pintype "passive"))
      (node (ref "C30") (pin "-") (pinfunction "-_-") (pintype "passive"))
      (node (ref "C33") (pin "2") (pinfunction "2_2") (pintype "passive"))
      (node (ref "C34") (pin "2") (pinfunction "2_2") (pintype "passive"))
      (node (ref "C6") (pin "1") (pinfunction "1_1") (pintype "passive"))
      (node (ref "GND") (pin "1") (pinfunction "3_1") (pintype "passive"))
      (node (ref "GND1") (pin "1") (pinfunction "3_1") (pintype "passive"))
      (node (ref "GND10") (pin "1") (pinfunction "3_1") (pintype "passive"))
      (node (ref "GND11") (pin "1") (pinfunction "3_1") (pintype "passive"))
      (node (ref "GND2") (pin "1") (pinfunction "3_1") (pintype "passive"))
      (node (ref "GND3") (pin "1") (pinfunction "3_1") (pintype "passive"))
      (node (ref "GND4") (pin "1") (pinfunction "3_1") (pintype "passive"))
      (node (ref "GND5") (pin "1") (pinfunction "3_1") (pintype "passive"))
      (node (ref "GND6") (pin "1") (pinfunction "3_1") (pintype "passive"))
      (node (ref "GND7") (pin "1") (pinfunction "3_1") (pintype "passive"))
      (node (ref "GND8") (pin "1") (pinfunction "3_1") (pintype "passive"))
      (node (ref "GND9") (pin "1") (pinfunction "3_1") (pintype "passive"))
      (node (ref "IC1") (pin "10") (pinfunction "+IN_10") (pintype "input"))
      (node (ref "IC1") (pin "12") (pinfunction "+IN_12") (pintype "input"))
      (node (ref "IC1") (pin "3") (pinfunction "+IN_3") (pintype "input"))
      (node (ref "IC1") (pin "5") (pinfunction "+IN_5") (pintype "input"))
      (node (ref "IC10") (pin "13") (pinfunction "A0_13") (pintype "input"))
      (node (ref "IC10") (pin "14") (pinfunction "A1_14") (pintype "input"))
      (node (ref "IC10") (pin "15") (pinfunction "~{ENABLE}_15") (pintype "input"))
      (node (ref "IC10") (pin "16") (pinfunction "LDAC_16") (pintype "input"))
      (node (ref "IC10") (pin "5") (pinfunction "VREFL_5") (pintype "input"))
      (node (ref "IC10") (pin "6") (pinfunction "GND_6") (pintype "power_in"))
      (node (ref "IC11") (pin "13") (pinfunction "A0_13") (pintype "input"))
      (node (ref "IC11") (pin "14") (pinfunction "A1_14") (pintype "input"))
      (node (ref "IC11") (pin "15") (pinfunction "~{ENABLE}_15") (pintype "input"))
      (node (ref "IC11") (pin "16") (pinfunction "LDAC_16") (pintype "input"))
      (node (ref "IC11") (pin "5") (pinfunction "VREFL_5") (pintype "input"))
      (node (ref "IC11") (pin "6") (pinfunction "GND_6") (pintype "power_in"))
      (node (ref "IC3") (pin "10") (pinfunction "+IN_10") (pintype "input"))
      (node (ref "IC3") (pin "11") (pinfunction "V-_11") (pintype "power_in"))
      (node (ref "IC3") (pin "12") (pinfunction "+IN_12") (pintype "input"))
      (node (ref "IC3") (pin "3") (pinfunction "+IN_3") (pintype "input"))
      (node (ref "IC3") (pin "5") (pinfunction "+IN_5") (pintype "input"))
      (node (ref "IC4") (pin "10") (pinfunction "+IN_10") (pintype "input"))
      (node (ref "IC4") (pin "11") (pinfunction "V-_11") (pintype "power_in"))
      (node (ref "IC4") (pin "12") (pinfunction "+IN_12") (pintype "input"))
      (node (ref "IC4") (pin "3") (pinfunction "+IN_3") (pintype "input"))
      (node (ref "IC4") (pin "5") (pinfunction "+IN_5") (pintype "input"))
      (node (ref "IC5") (pin "10") (pinfunction "+IN_10") (pintype "input"))
      (node (ref "IC5") (pin "12") (pinfunction "+IN_12") (pintype "input"))
      (node (ref "IC5") (pin "3") (pinfunction "+IN_3") (pintype "input"))
      (node (ref "IC5") (pin "5") (pinfunction "+IN_5") (pintype "input"))
      (node (ref "IC6") (pin "GND1") (pinfunction "GND1_GND1") (pintype "bidirectional"))
      (node (ref "IC6") (pin "GND3") (pinfunction "GND3_GND3") (pintype "bidirectional"))
      (node (ref "IC6") (pin "GND6") (pinfunction "GND6_GND6") (pintype "bidirectional"))
      (node (ref "IC7") (pin "2") (pinfunction "GND_2") (pintype "passive"))
      (node (ref "IC8") (pin "1") (pinfunction "C_1") (pintype "input"))
      (node (ref "IC9") (pin "2") (pinfunction "GND_2") (pintype "power_in"))
      (node (ref "IC9") (pin "2-2") (pinfunction "GND_2-2") (pintype "power_in"))
    )
    (net (code "41") (name "Net-(0_RX-3)") (class "Default")
      (node (ref "0_RX") (pin "1") (pinfunction "3_1") (pintype "passive"))
      (node (ref "IC6") (pin "0-RX1/CS1/CRX2") (pinfunction "0-RX1/CS1/CRX2_0-RX1/CS1/CRX2") (pintype "bidirectional"))
    )
    (net (code "42") (name "Net-(1_TX-3)") (class "Default")
      (node (ref "1_TX") (pin "1") (pinfunction "3_1") (pintype "passive"))
      (node (ref "IC6") (pin "1-TX1/MISO1/CTX2") (pinfunction "1-TX1/MISO1/CTX2_1-TX1/MISO1/CTX2") (pintype "bidirectional"))
    )
    (net (code "43") (name "Net-(2-3)") (class "Default")
      (node (ref "2") (pin "1") (pinfunction "3_1") (pintype "passive"))
      (node (ref "IC6") (pin "2-OUT2") (pinfunction "2-OUT2_2-OUT2") (pintype "bidirectional"))
    )
    (net (code "44") (name "Net-(3-3)") (class "Default")
      (node (ref "3") (pin "1") (pinfunction "3_1") (pintype "passive"))
      (node (ref "IC6") (pin "3-LRCLK2") (pinfunction "3-LRCLK2_3-LRCLK2") (pintype "bidirectional"))
    )
    (net (code "45") (name "Net-(4-3)") (class "Default")
      (node (ref "4") (pin "1") (pinfunction "3_1") (pintype "passive"))
      (node (ref "IC6") (pin "4-BCLK2") (pinfunction "4-BCLK2_4-BCLK2") (pintype "bidirectional"))
    )
    (net (code "46") (name "Net-(5-3)") (class "Default")
      (node (ref "5") (pin "1") (pinfunction "3_1") (pintype "passive"))
      (node (ref "IC6") (pin "5-IN2") (pinfunction "5-IN2_5-IN2") (pintype "bidirectional"))
    )
    (net (code "47") (name "Net-(18_A4_SDA-3)") (class "Default")
      (node (ref "18_A4_SDA") (pin "1") (pinfunction "3_1") (pintype "passive"))
      (node (ref "IC6") (pin "18-A4/SDA0") (pinfunction "18-A4/SDA0_18-A4/SDA0") (pintype "bidirectional"))
      (node (ref "R115") (pin "1") (pinfunction "1_1") (pintype "passive"))
    )
    (net (code "48") (name "Net-(19_A5_SCL-3)") (class "Default")
      (node (ref "19_A5_SCL") (pin "1") (pinfunction "3_1") (pintype "passive"))
      (node (ref "IC6") (pin "19-A5/SCL0") (pinfunction "19-A5/SCL0_19-A5/SCL0") (pintype "bidirectional"))
      (node (ref "R116") (pin "1") (pinfunction "1_1") (pintype "passive"))
    )
    (net (code "49") (name "Net-(28-3)") (class "Default")
      (node (ref "28") (pin "1") (pinfunction "3_1") (pintype "passive"))
      (node (ref "IC6") (pin "28-RX7") (pinfunction "28-RX7_28-RX7") (pintype "bidirectional"))
    )
    (net (code "50") (name "Net-(29-3)") (class "Default")
      (node (ref "29") (pin "1") (pinfunction "3_1") (pintype "passive"))
      (node (ref "IC6") (pin "29-TX7") (pinfunction "29-TX7_29-TX7") (pintype "bidirectional"))
    )
    (net (code "51") (name "Net-(30-3)") (class "Default")
      (node (ref "30") (pin "1") (pinfunction "3_1") (pintype "passive"))
      (node (ref "IC6") (pin "30-CRX3") (pinfunction "30-CRX3_30-CRX3") (pintype "bidirectional"))
    )
    (net (code "52") (name "Net-(31-3)") (class "Default")
      (node (ref "31") (pin "1") (pinfunction "3_1") (pintype "passive"))
      (node (ref "IC6") (pin "31-CTX3") (pinfunction "31-CTX3_31-CTX3") (pintype "bidirectional"))
    )
    (net (code "53") (name "Net-(32-3)") (class "Default")
      (node (ref "32") (pin "1") (pinfunction "3_1") (pintype "passive"))
      (node (ref "IC6") (pin "32-OUT1B") (pinfunction "32-OUT1B_32-OUT1B") (pintype "bidirectional"))
    )
    (net (code "54") (name "Net-(33-3)") (class "Default")
      (node (ref "33") (pin "1") (pinfunction "3_1") (pintype "passive"))
      (node (ref "IC6") (pin "33-MCLK2") (pinfunction "33-MCLK2_33-MCLK2") (pintype "bidirectional"))
    )
    (net (code "55") (name "Net-(34-3)") (class "Default")
      (node (ref "34") (pin "1") (pinfunction "3_1") (pintype "passive"))
      (node (ref "IC6") (pin "34-RX8") (pinfunction "34-RX8_34-RX8") (pintype "bidirectional"))
    )
    (net (code "56") (name "Net-(35-3)") (class "Default")
      (node (ref "35") (pin "1") (pinfunction "3_1") (pintype "passive"))
      (node (ref "IC6") (pin "35-TX8") (pinfunction "35/TX8_35-TX8") (pintype "bidirectional"))
    )
    (net (code "57") (name "Net-(36-3)") (class "Default")
      (node (ref "36") (pin "1") (pinfunction "3_1") (pintype "passive"))
      (node (ref "IC6") (pin "36-PWM") (pinfunction "36-PWM_36-PWM") (pintype "bidirectional"))
    )
    (net (code "58") (name "Net-(37-3)") (class "Default")
      (node (ref "37") (pin "1") (pinfunction "3_1") (pintype "passive"))
      (node (ref "IC6") (pin "37-PWM") (pinfunction "37-PWM_37-PWM") (pintype "bidirectional"))
    )
    (net (code "59") (name "Net-(CV1-3)") (class "Default")
      (node (ref "CV1") (pin "1") (pinfunction "3_1") (pintype "passive"))
      (node (ref "R31") (pin "1") (pinfunction "1_1") (pintype "passive"))
    )
    (net (code "60") (name "Net-(CV1B-3)") (class "Default")
      (node (ref "CV1B") (pin "1") (pinfunction "3_1") (pintype "passive"))
      (node (ref "R32") (pin "1") (pinfunction "1_1") (pintype "passive"))
    )
    (net (code "61") (name "Net-(CV2-3)") (class "Default")
      (node (ref "CV2") (pin "1") (pinfunction "3_1") (pintype "passive"))
      (node (ref "R27") (pin "1") (pinfunction "1_1") (pintype "passive"))
    )
    (net (code "62") (name "Net-(CV2B-3)") (class "Default")
      (node (ref "CV2B") (pin "1") (pinfunction "3_1") (pintype "passive"))
      (node (ref "R28") (pin "1") (pinfunction "1_1") (pintype "passive"))
    )
    (net (code "63") (name "Net-(CV3-3)") (class "Default")
      (node (ref "CV3") (pin "1") (pinfunction "3_1") (pintype "passive"))
      (node (ref "R22") (pin "1") (pinfunction "1_1") (pintype "passive"))
    )
    (net (code "64") (name "Net-(CV3B-3)") (class "Default")
      (node (ref "CV3B") (pin "1") (pinfunction "3_1") (pintype "passive"))
      (node (ref "R23") (pin "1") (pinfunction "1_1") (pintype "passive"))
    )
    (net (code "65") (name "Net-(CV4-3)") (class "Default")
      (node (ref "CV4") (pin "1") (pinfunction "3_1") (pintype "passive"))
      (node (ref "R35") (pin "1") (pinfunction "1_1") (pintype "passive"))
    )
    (net (code "66") (name "Net-(CV4B-3)") (class "Default")
      (node (ref "CV4B") (pin "1") (pinfunction "3_1") (pintype "passive"))
      (node (ref "R36") (pin "1") (pinfunction "1_1") (pintype "passive"))
    )
    (net (code "67") (name "Net-(CV5-3)") (class "Default")
      (node (ref "CV5") (pin "1") (pinfunction "3_1") (pintype "passive"))
      (node (ref "R65") (pin "1") (pinfunction "1_1") (pintype "passive"))
    )
    (net (code "68") (name "Net-(CV5B-3)") (class "Default")
      (node (ref "CV5B") (pin "1") (pinfunction "3_1") (pintype "passive"))
      (node (ref "R66") (pin "1") (pinfunction "1_1") (pintype "passive"))
    )
    (net (code "69") (name "Net-(CV6-3)") (class "Default")
      (node (ref "CV6") (pin "1") (pinfunction "3_1") (pintype "passive"))
      (node (ref "R62") (pin "1") (pinfunction "1_1") (pintype "passive"))
    )
    (net (code "70") (name "Net-(CV6B-3)") (class "Default")
      (node (ref "CV6B") (pin "1") (pinfunction "3_1") (pintype "passive"))
      (node (ref "R63") (pin "1") (pinfunction "1_1") (pintype "passive"))
    )
    (net (code "71") (name "Net-(CV7-3)") (class "Default")
      (node (ref "CV7") (pin "1") (pinfunction "3_1") (pintype "passive"))
      (node (ref "R11") (pin "1") (pinfunction "1_1") (pintype "passive"))
    )
    (net (code "72") (name "Net-(CV7B-3)") (class "Default")
      (node (ref "CV7B") (pin "1") (pinfunction "3_1") (pintype "passive"))
      (node (ref "R12") (pin "1") (pinfunction "1_1") (pintype "passive"))
    )
    (net (code "73") (name "Net-(CV8-3)") (class "Default")
      (node (ref "CV8") (pin "1") (pinfunction "3_1") (pintype "passive"))
      (node (ref "R69") (pin "1") (pinfunction "1_1") (pintype "passive"))
    )
    (net (code "74") (name "Net-(CV8B-3)") (class "Default")
      (node (ref "CV8B") (pin "1") (pinfunction "3_1") (pintype "passive"))
      (node (ref "R70") (pin "1") (pinfunction "1_1") (pintype "passive"))
    )
    (net (code "75") (name "Net-(CVO1-3)") (class "Default")
      (node (ref "CVO1") (pin "1") (pinfunction "3_1") (pintype "passive"))
      (node (ref "R45") (pin "2") (pinfunction "2_2") (pintype "passive"))
      (node (ref "R47") (pin "2") (pinfunction "2_2") (pintype "passive"))
    )
    (net (code "76") (name "Net-(CVO2-3)") (class "Default")
      (node (ref "CVO2") (pin "1") (pinfunction "3_1") (pintype "passive"))
      (node (ref "R19") (pin "2") (pinfunction "2_2") (pintype "passive"))
      (node (ref "R38") (pin "2") (pinfunction "2_2") (pintype "passive"))
    )
    (net (code "77") (name "Net-(CVO3-3)") (class "Default")
      (node (ref "CVO3") (pin "1") (pinfunction "3_1") (pintype "passive"))
      (node (ref "R39") (pin "2") (pinfunction "2_2") (pintype "passive"))
      (node (ref "R41") (pin "2") (pinfunction "2_2") (pintype "passive"))
    )
    (net (code "78") (name "Net-(CVO4-3)") (class "Default")
      (node (ref "CVO4") (pin "1") (pinfunction "3_1") (pintype "passive"))
      (node (ref "R42") (pin "2") (pinfunction "2_2") (pintype "passive"))
      (node (ref "R44") (pin "2") (pinfunction "2_2") (pintype "passive"))
    )
    (net (code "79") (name "Net-(CVO5-3)") (class "Default")
      (node (ref "CVO5") (pin "1") (pinfunction "3_1") (pintype "passive"))
      (node (ref "R16") (pin "2") (pinfunction "2_2") (pintype "passive"))
      (node (ref "R18") (pin "2") (pinfunction "2_2") (pintype "passive"))
    )
    (net (code "80") (name "Net-(CVO6-3)") (class "Default")
      (node (ref "CVO6") (pin "1") (pinfunction "3_1") (pintype "passive"))
      (node (ref "R1") (pin "2") (pinfunction "2_2") (pintype "passive"))
      (node (ref "R3") (pin "2") (pinfunction "2_2") (pintype "passive"))
    )
    (net (code "81") (name "Net-(CVO7-3)") (class "Default")
      (node (ref "CVO7") (pin "1") (pinfunction "3_1") (pintype "passive"))
      (node (ref "R4") (pin "2") (pinfunction "2_2") (pintype "passive"))
      (node (ref "R6") (pin "2") (pinfunction "2_2") (pintype "passive"))
    )
    (net (code "82") (name "Net-(CVO8-3)") (class "Default")
      (node (ref "CVO8") (pin "1") (pinfunction "3_1") (pintype "passive"))
      (node (ref "R14") (pin "2") (pinfunction "2_2") (pintype "passive"))
      (node (ref "R9") (pin "2") (pinfunction "2_2") (pintype "passive"))
    )
    (net (code "83") (name "Net-(IC1A--IN)") (class "Default")
      (node (ref "C4") (pin "1") (pinfunction "1_1") (pintype "passive"))
      (node (ref "IC1") (pin "2") (pinfunction "-IN_2") (pintype "input"))
      (node (ref "R1") (pin "1") (pinfunction "1_1") (pintype "passive"))
      (node (ref "R2") (pin "2") (pinfunction "2_2") (pintype "passive"))
      (node (ref "R48") (pin "2") (pinfunction "2_2") (pintype "passive"))
      (node (ref "R83") (pin "2") (pinfunction "2_2") (pintype "passive"))
    )
    (net (code "84") (name "Net-(IC1A-OUT)") (class "Default")
      (node (ref "C4") (pin "2") (pinfunction "2_2") (pintype "passive"))
      (node (ref "IC1") (pin "1") (pinfunction "OUT_1") (pintype "output"))
      (node (ref "R3") (pin "1") (pinfunction "1_1") (pintype "passive"))
    )
    (net (code "85") (name "Net-(IC1B--IN)") (class "Default")
      (node (ref "C5") (pin "1") (pinfunction "1_1") (pintype "passive"))
      (node (ref "IC1") (pin "6") (pinfunction "-IN_6") (pintype "input"))
      (node (ref "R4") (pin "1") (pinfunction "1_1") (pintype "passive"))
      (node (ref "R49") (pin "2") (pinfunction "2_2") (pintype "passive"))
      (node (ref "R5") (pin "2") (pinfunction "2_2") (pintype "passive"))
      (node (ref "R84") (pin "2") (pinfunction "2_2") (pintype "passive"))
    )
    (net (code "86") (name "Net-(IC1B-OUT)") (class "Default")
      (node (ref "C5") (pin "2") (pinfunction "2_2") (pintype "passive"))
      (node (ref "IC1") (pin "7") (pinfunction "OUT_7") (pintype "output"))
      (node (ref "R6") (pin "1") (pinfunction "1_1") (pintype "passive"))
    )
    (net (code "87") (name "Net-(IC1C--IN)") (class "Default")
      (node (ref "C8") (pin "1") (pinfunction "1_1") (pintype "passive"))
      (node (ref "IC1") (pin "9") (pinfunction "-IN_9") (pintype "input"))
      (node (ref "R10") (pin "2") (pinfunction "2_2") (pintype "passive"))
      (node (ref "R50") (pin "2") (pinfunction "2_2") (pintype "passive"))
      (node (ref "R85") (pin "2") (pinfunction "2_2") (pintype "passive"))
      (node (ref "R9") (pin "1") (pinfunction "1_1") (pintype "passive"))
    )
    (net (code "88") (name "Net-(IC1C-OUT)") (class "Default")
      (node (ref "C8") (pin "2") (pinfunction "2_2") (pintype "passive"))
      (node (ref "IC1") (pin "8") (pinfunction "OUT_8") (pintype "output"))
      (node (ref "R14") (pin "1") (pinfunction "1_1") (pintype "passive"))
    )
    (net (code "89") (name "Net-(IC1D--IN)") (class "Default")
      (node (ref "C9") (pin "1") (pinfunction "1_1") (pintype "passive"))
      (node (ref "IC1") (pin "13") (pinfunction "-IN_13") (pintype "input"))
      (node (ref "R16") (pin "1") (pinfunction "1_1") (pintype "passive"))
      (node (ref "R17") (pin "2") (pinfunction "2_2") (pintype "passive"))
      (node (ref "R51") (pin "2") (pinfunction "2_2") (pintype "passive"))
      (node (ref "R86") (pin "2") (pinfunction "2_2") (pintype "passive"))
    )
    (net (code "90") (name "Net-(IC1D-OUT)") (class "Default")
      (node (ref "C9") (pin "2") (pinfunction "2_2") (pintype "passive"))
      (node (ref "IC1") (pin "14") (pinfunction "OUT_14") (pintype "output"))
      (node (ref "R18") (pin "1") (pinfunction "1_1") (pintype "passive"))
    )
    (net (code "91") (name "Net-(IC3A--IN)") (class "Default")
      (node (ref "C7") (pin "1") (pinfunction "1_1") (pintype "passive"))
      (node (ref "IC3") (pin "2") (pinfunction "-IN_2") (pintype "input"))
      (node (ref "R11") (pin "2") (pinfunction "2_2") (pintype "passive"))
      (node (ref "R12") (pin "2") (pinfunction "2_2") (pintype "passive"))
      (node (ref "R13") (pin "2") (pinfunction "2_2") (pintype "passive"))
      (node (ref "R8") (pin "1") (pinfunction "1_1") (pintype "passive"))
    )
    (net (code "92") (name "Net-(IC3B--IN)") (class "Default")
      (node (ref "C10") (pin "1") (pinfunction "1_1") (pintype "passive"))
      (node (ref "IC3") (pin "6") (pinfunction "-IN_6") (pintype "input"))
      (node (ref "R15") (pin "1") (pinfunction "1_1") (pintype "passive"))
      (node (ref "R29") (pin "2") (pinfunction "2_2") (pintype "passive"))
      (node (ref "R62") (pin "2") (pinfunction "2_2") (pintype "passive"))
      (node (ref "R63") (pin "2") (pinfunction "2_2") (pintype "passive"))
    )
    (net (code "93") (name "Net-(IC3C--IN)") (class "Default")
      (node (ref "C11") (pin "1") (pinfunction "1_1") (pintype "passive"))
      (node (ref "IC3") (pin "9") (pinfunction "-IN_9") (pintype "input"))
      (node (ref "R64") (pin "1") (pinfunction "1_1") (pintype "passive"))
      (node (ref "R65") (pin "2") (pinfunction "2_2") (pintype "passive"))
      (node (ref "R66") (pin "2") (pinfunction "2_2") (pintype "passive"))
      (node (ref "R67") (pin "2") (pinfunction "2_2") (pintype "passive"))
    )
    (net (code "94") (name "Net-(IC3D--IN)") (class "Default")
      (node (ref "C14") (pin "1") (pinfunction "1_1") (pintype "passive"))
      (node (ref "IC3") (pin "13") (pinfunction "-IN_13") (pintype "input"))
      (node (ref "R68") (pin "1") (pinfunction "1_1") (pintype "passive"))
      (node (ref "R69") (pin "2") (pinfunction "2_2") (pintype "passive"))
      (node (ref "R70") (pin "2") (pinfunction "2_2") (pintype "passive"))
      (node (ref "R71") (pin "2") (pinfunction "2_2") (pintype "passive"))
    )
    (net (code "95") (name "Net-(IC4A--IN)") (class "Default")
      (node (ref "C16") (pin "1") (pinfunction "1_1") (pintype "passive"))
      (node (ref "IC4") (pin "2") (pinfunction "-IN_2") (pintype "input"))
      (node (ref "R21") (pin "1") (pinfunction "1_1") (pintype "passive"))
      (node (ref "R22") (pin "2") (pinfunction "2_2") (pintype "passive"))
      (node (ref "R23") (pin "2") (pinfunction "2_2") (pintype "passive"))
      (node (ref "R24") (pin "2") (pinfunction "2_2") (pintype "passive"))
    )
    (net (code "96") (name "Net-(IC4B--IN)") (class "Default")
      (node (ref "C17") (pin "1") (pinfunction "1_1") (pintype "passive"))
      (node (ref "IC4") (pin "6") (pinfunction "-IN_6") (pintype "input"))
      (node (ref "R25") (pin "1") (pinfunction "1_1") (pintype "passive"))
      (node (ref "R26") (pin "2") (pinfunction "2_2") (pintype "passive"))
      (node (ref "R27") (pin "2") (pinfunction "2_2") (pintype "passive"))
      (node (ref "R28") (pin "2") (pinfunction "2_2") (pintype "passive"))
    )
    (net (code "97") (name "Net-(IC4C--IN)") (class "Default")
      (node (ref "C20") (pin "1") (pinfunction "1_1") (pintype "passive"))
      (node (ref "IC4") (pin "9") (pinfunction "-IN_9") (pintype "input"))
      (node (ref "R30") (pin "1") (pinfunction "1_1") (pintype "passive"))
      (node (ref "R31") (pin "2") (pinfunction "2_2") (pintype "passive"))
      (node (ref "R32") (pin "2") (pinfunction "2_2") (pintype "passive"))
      (node (ref "R33") (pin "2") (pinfunction "2_2") (pintype "passive"))
    )
    (net (code "98") (name "Net-(IC4D--IN)") (class "Default")
      (node (ref "C21") (pin "1") (pinfunction "1_1") (pintype "passive"))
      (node (ref "IC4") (pin "13") (pinfunction "-IN_13") (pintype "input"))
      (node (ref "R34") (pin "1") (pinfunction "1_1") (pintype "passive"))
      (node (ref "R35") (pin "2") (pinfunction "2_2") (pintype "passive"))
      (node (ref "R36") (pin "2") (pinfunction "2_2") (pintype "passive"))
      (node (ref "R37") (pin "2") (pinfunction "2_2") (pintype "passive"))
    )
    (net (code "99") (name "Net-(IC5A--IN)") (class "Default")
      (node (ref "C12") (pin "1") (pinfunction "1_1") (pintype "passive"))
      (node (ref "IC5") (pin "2") (pinfunction "-IN_2") (pintype "input"))
      (node (ref "R19") (pin "1") (pinfunction "1_1") (pintype "passive"))
      (node (ref "R20") (pin "2") (pinfunction "2_2") (pintype "passive"))
      (node (ref "R52") (pin "2") (pinfunction "2_2") (pintype "passive"))
      (node (ref "R90") (pin "2") (pinfunction "2_2") (pintype "passive"))
    )
    (net (code "100") (name "Net-(IC5A-OUT)") (class "Default")
      (node (ref "C12") (pin "2") (pinfunction "2_2") (pintype "passive"))
      (node (ref "IC5") (pin "1") (pinfunction "OUT_1") (pintype "output"))
      (node (ref "R38") (pin "1") (pinfunction "1_1") (pintype "passive"))
    )
    (net (code "101") (name "Net-(IC5B--IN)") (class "Default")
      (node (ref "C13") (pin "1") (pinfunction "1_1") (pintype "passive"))
      (node (ref "IC5") (pin "6") (pinfunction "-IN_6") (pintype "input"))
      (node (ref "R39") (pin "1") (pinfunction "1_1") (pintype "passive"))
      (node (ref "R40") (pin "2") (pinfunction "2_2") (pintype "passive"))
      (node (ref "R53") (pin "2") (pinfunction "2_2") (pintype "passive"))
      (node (ref "R89") (pin "2") (pinfunction "2_2") (pintype "passive"))
    )
    (net (code "102") (name "Net-(IC5B-OUT)") (class "Default")
      (node (ref "C13") (pin "2") (pinfunction "2_2") (pintype "passive"))
      (node (ref "IC5") (pin "7") (pinfunction "OUT_7") (pintype "output"))
      (node (ref "R41") (pin "1") (pinfunction "1_1") (pintype "passive"))
    )
    (net (code "103") (name "Net-(IC5C--IN)") (class "Default")
      (node (ref "C19") (pin "1") (pinfunction "1_1") (pintype "passive"))
      (node (ref "IC5") (pin "9") (pinfunction "-IN_9") (pintype "input"))
      (node (ref "R42") (pin "1") (pinfunction "1_1") (pintype "passive"))
      (node (ref "R43") (pin "2") (pinfunction "2_2") (pintype "passive"))
      (node (ref "R54") (pin "2") (pinfunction "2_2") (pintype "passive"))
      (node (ref "R88") (pin "2") (pinfunction "2_2") (pintype "passive"))
    )
    (net (code "104") (name "Net-(IC5C-OUT)") (class "Default")
      (node (ref "C19") (pin "2") (pinfunction "2_2") (pintype "passive"))
      (node (ref "IC5") (pin "8") (pinfunction "OUT_8") (pintype "output"))
      (node (ref "R44") (pin "1") (pinfunction "1_1") (pintype "passive"))
    )
    (net (code "105") (name "Net-(IC5D--IN)") (class "Default")
      (node (ref "C22") (pin "1") (pinfunction "1_1") (pintype "passive"))
      (node (ref "IC5") (pin "13") (pinfunction "-IN_13") (pintype "input"))
      (node (ref "R45") (pin "1") (pinfunction "1_1") (pintype "passive"))
      (node (ref "R46") (pin "2") (pinfunction "2_2") (pintype "passive"))
      (node (ref "R55") (pin "2") (pinfunction "2_2") (pintype "passive"))
      (node (ref "R87") (pin "2") (pinfunction "2_2") (pintype "passive"))
    )
    (net (code "106") (name "Net-(IC5D-OUT)") (class "Default")
      (node (ref "C22") (pin "2") (pinfunction "2_2") (pintype "passive"))
      (node (ref "IC5") (pin "14") (pinfunction "OUT_14") (pintype "output"))
      (node (ref "R47") (pin "1") (pinfunction "1_1") (pintype "passive"))
    )
    (net (code "107") (name "Net-(IC7-VI)") (class "Default")
      (node (ref "C28") (pin "2") (pinfunction "2_2") (pintype "passive"))
      (node (ref "IC7") (pin "1") (pinfunction "VI_1") (pintype "input"))
      (node (ref "L1") (pin "2") (pinfunction "2_2") (pintype "passive"))
    )
    (net (code "108") (name "Net-(IC9-VIN)") (class "Default")
      (node (ref "C29") (pin "2") (pinfunction "2_2") (pintype "passive"))
      (node (ref "IC9") (pin "3") (pinfunction "VIN_3") (pintype "power_in"))
      (node (ref "L2") (pin "2") (pinfunction "2_2") (pintype "passive"))
    )
    (net (code "109") (name "Net-(IC10-VREFH{slash}VREFOUT)") (class "Default")
      (node (ref "C34") (pin "1") (pinfunction "1_1") (pintype "passive"))
      (node (ref "IC10") (pin "3") (pinfunction "VREFH/VREFOUT_3") (pintype "bidirectional"))
    )
    (net (code "110") (name "Net-(IC11-VREFH{slash}VREFOUT)") (class "Default")
      (node (ref "C33") (pin "1") (pinfunction "1_1") (pintype "passive"))
      (node (ref "IC11") (pin "3") (pinfunction "VREFH/VREFOUT_3") (pintype "bidirectional"))
    )
    (net (code "111") (name "unconnected-(IC6-Pad3V3-1)") (class "Default")
      (node (ref "IC6") (pin "3V3-1") (pinfunction "3V3-1_3V3-1") (pintype "bidirectional"))
    )
  )
)
